# ArmazEthernet_-_Rev_A2.net
KiCad netlist of a schematic drawn in EAGLE
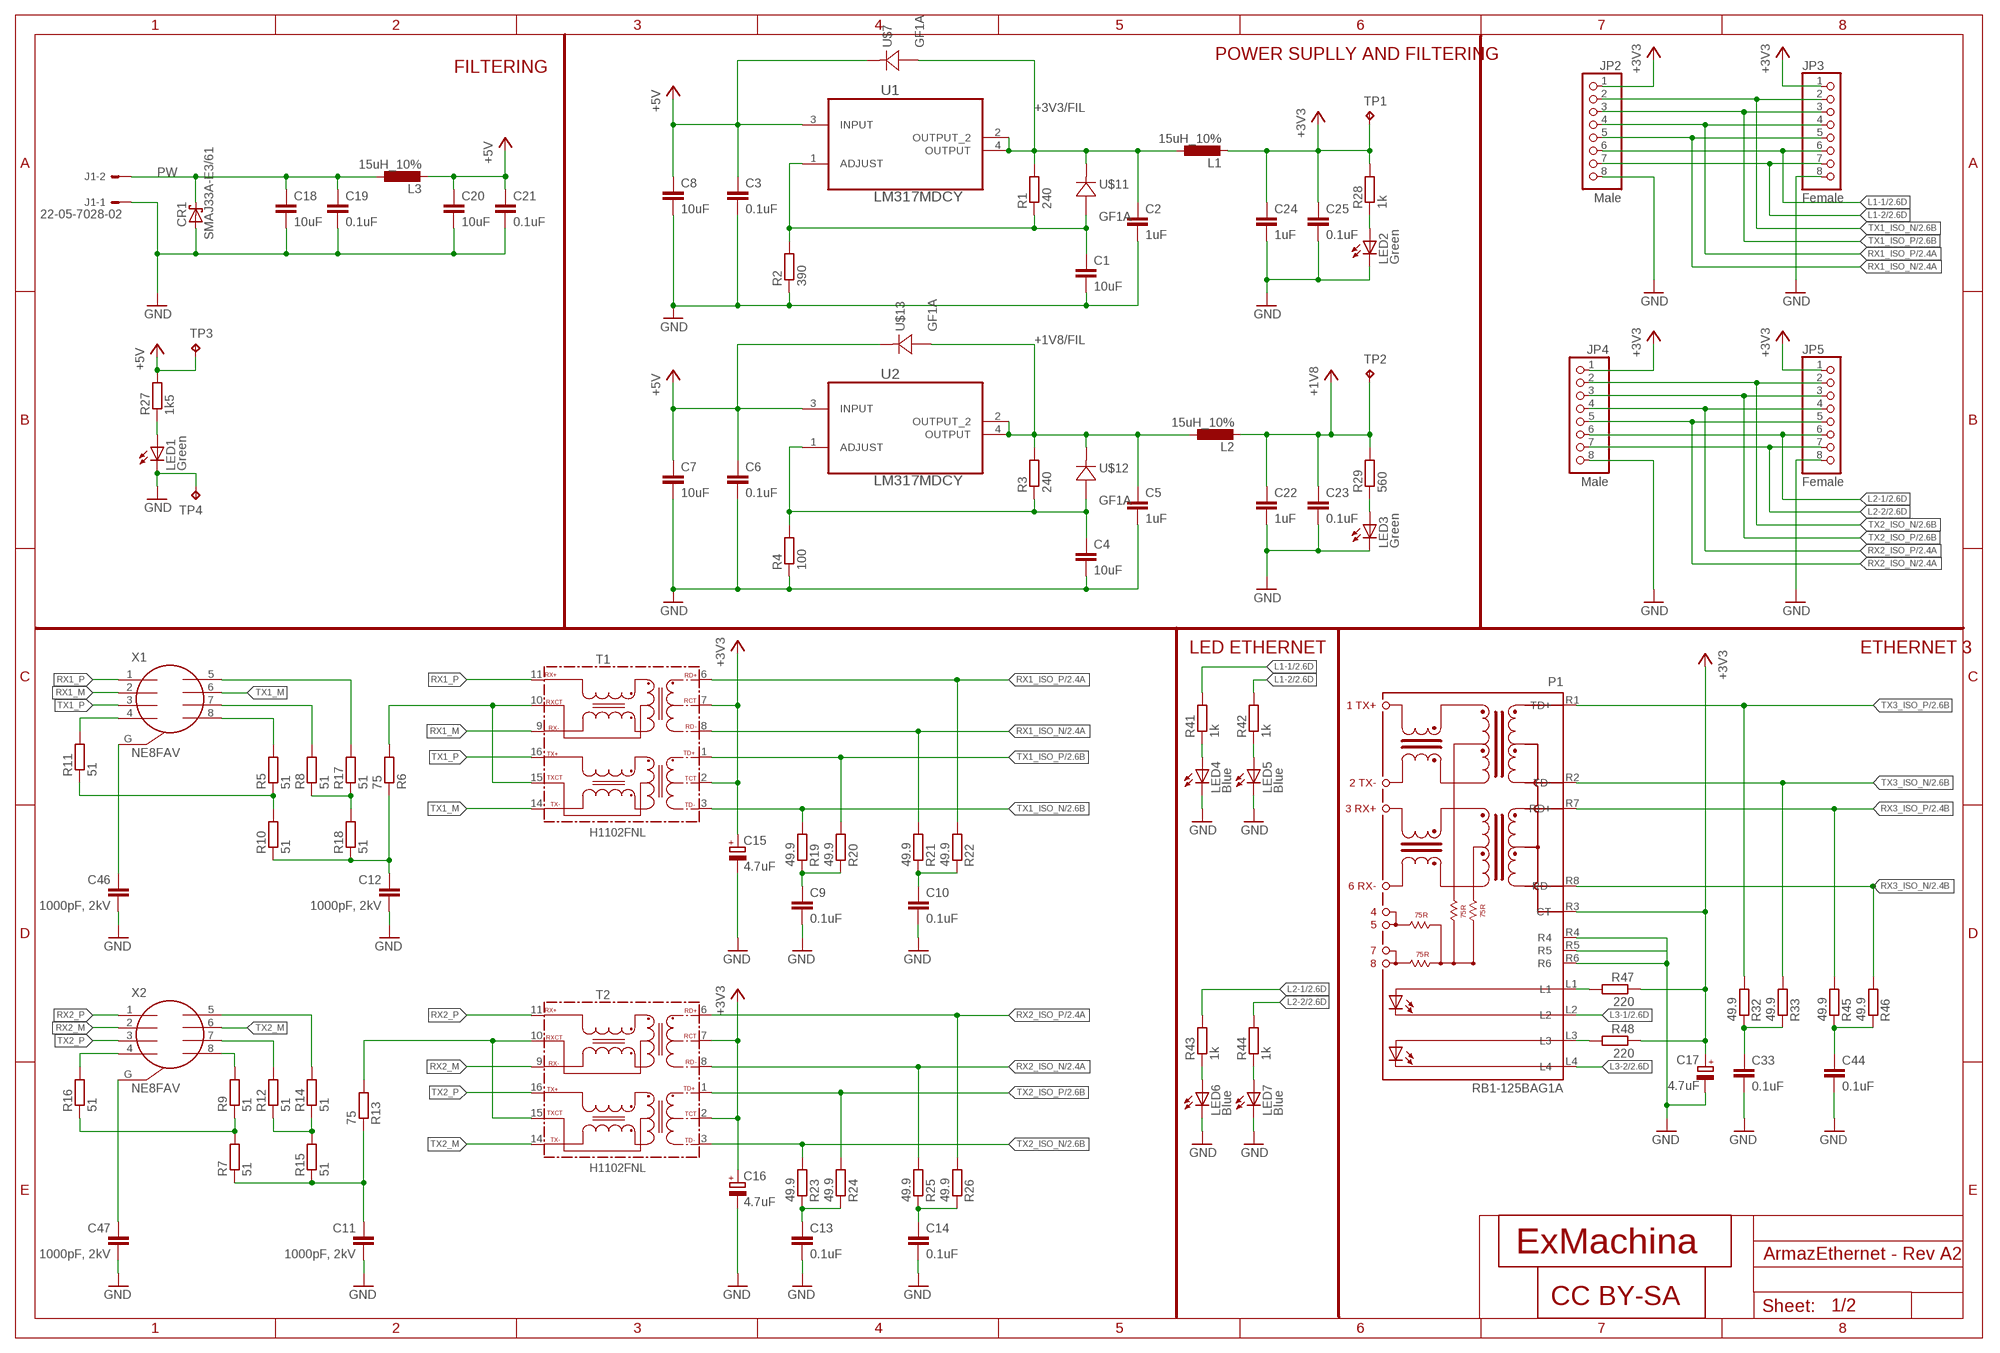
[diagram p0: schematic, sheet 1]
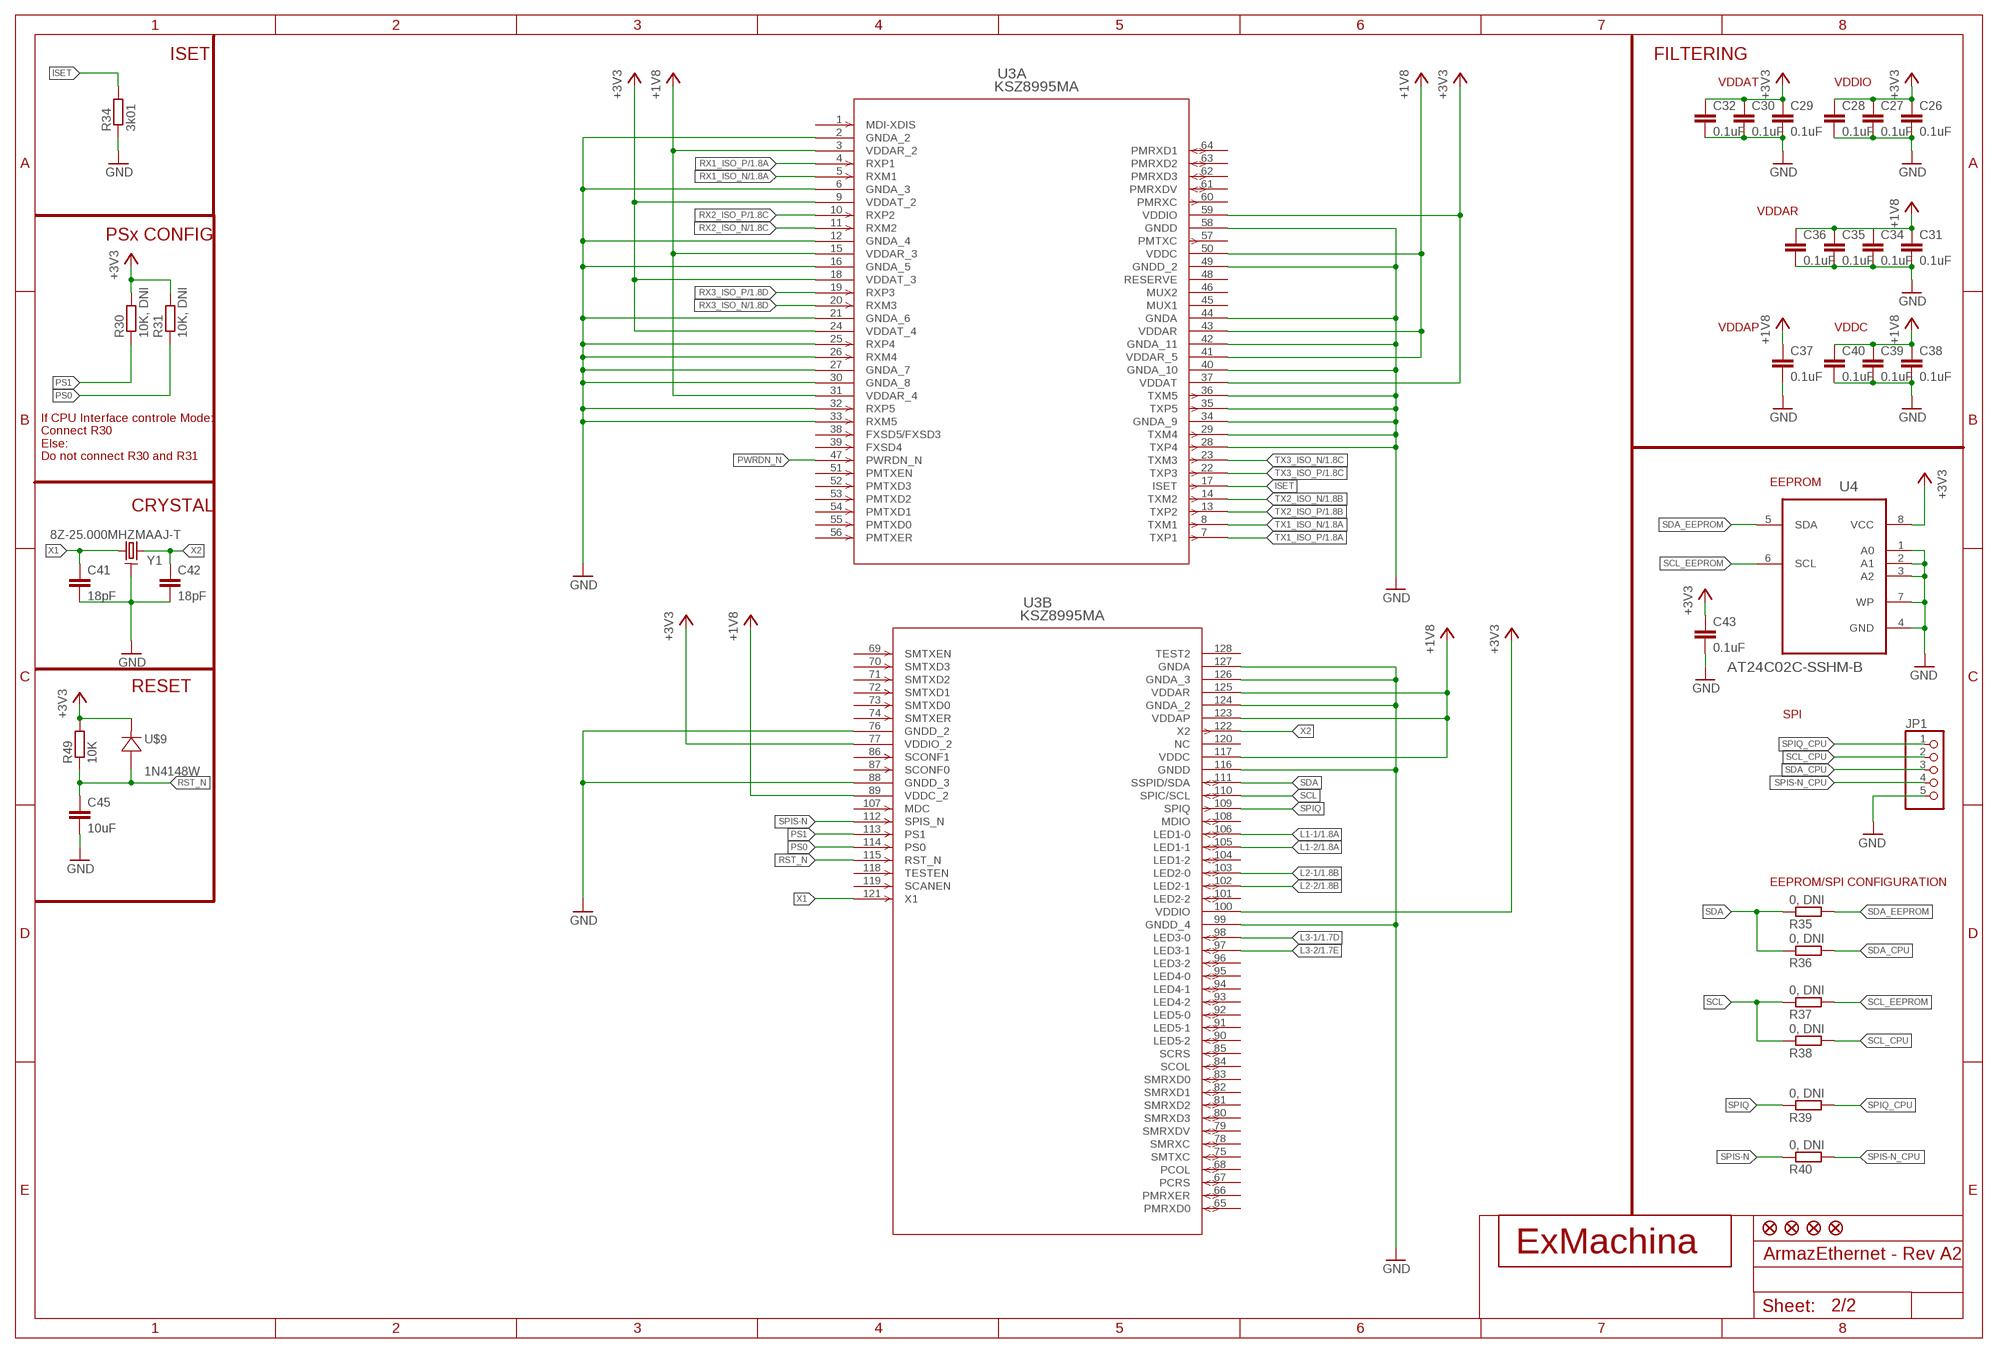
[diagram p1: schematic, sheet 2]

(export (version "E")
  (design (tool "Eeschema 10.0.6"))
  (components
    (comp (ref "C1")
      (value "10uF")
      (footprint "eagle-import:C0603")
      (fields (field (name "MPN") "MCNP16V106M5X11"))
      (libsource (lib "eagle-import") (part "C-EUC0603"))
    )
    (comp (ref "C2")
      (value "1uF")
      (footprint "eagle-import:C0603")
      (fields (field (name "MPN") "MC0603B105K160CT"))
      (libsource (lib "eagle-import") (part "C-EUC0603"))
    )
    (comp (ref "C3")
      (value "0.1uF")
      (footprint "eagle-import:C0603")
      (fields (field (name "MPN") "MC0603B104K160CT"))
      (libsource (lib "eagle-import") (part "C-EUC0603"))
    )
    (comp (ref "C4")
      (value "10uF")
      (footprint "eagle-import:C0603")
      (fields (field (name "MPN") "MCNP16V106M5X11"))
      (libsource (lib "eagle-import") (part "C-EUC0603"))
    )
    (comp (ref "C5")
      (value "1uF")
      (footprint "eagle-import:C0603")
      (fields (field (name "MPN") "MC0603B105K160CT"))
      (libsource (lib "eagle-import") (part "C-EUC0603"))
    )
    (comp (ref "C6")
      (value "0.1uF")
      (footprint "eagle-import:C0603")
      (fields (field (name "MPN") "MC0603B104K160CT"))
      (libsource (lib "eagle-import") (part "C-EUC0603"))
    )
    (comp (ref "C7")
      (value "10uF")
      (footprint "eagle-import:C0603")
      (fields (field (name "MPN") "MCNP16V106M5X11"))
      (libsource (lib "eagle-import") (part "C-EUC0603"))
    )
    (comp (ref "C8")
      (value "10uF")
      (footprint "eagle-import:C0603")
      (fields (field (name "MPN") "MCNP16V106M5X11"))
      (libsource (lib "eagle-import") (part "C-EUC0603"))
    )
    (comp (ref "C9")
      (value "0.1uF")
      (footprint "eagle-import:C0603")
      (fields (field (name "MPN") "MC0603B104K160CT"))
      (libsource (lib "eagle-import") (part "C-EUC0603"))
    )
    (comp (ref "C10")
      (value "0.1uF")
      (footprint "eagle-import:C0603")
      (fields (field (name "MPN") "MC0603B104K160CT"))
      (libsource (lib "eagle-import") (part "C-EUC0603"))
    )
    (comp (ref "C11")
      (value "1000pF, 2kV")
      (footprint "eagle-import:C1206")
      (fields (field (name "MPN") "MC1206B102K202CT"))
      (libsource (lib "eagle-import") (part "C-EUC1206"))
    )
    (comp (ref "C12")
      (value "1000pF, 2kV")
      (footprint "eagle-import:C1206")
      (fields (field (name "MPN") "MC1206B102K202CT"))
      (libsource (lib "eagle-import") (part "C-EUC1206"))
    )
    (comp (ref "C13")
      (value "0.1uF")
      (footprint "eagle-import:C0603")
      (fields (field (name "MPN") "MC0603B104K160CT"))
      (libsource (lib "eagle-import") (part "C-EUC0603"))
    )
    (comp (ref "C14")
      (value "0.1uF")
      (footprint "eagle-import:C0603")
      (fields (field (name "MPN") "MC0603B104K160CT"))
      (libsource (lib "eagle-import") (part "C-EUC0603"))
    )
    (comp (ref "C15")
      (value "4.7uF")
      (footprint "eagle-import:CT3216")
      (fields (field (name "MPN") "MCCTA475M010"))
      (libsource (lib "eagle-import") (part "CPOL-EUCT3216"))
    )
    (comp (ref "C16")
      (value "4.7uF")
      (footprint "eagle-import:CT3216")
      (fields (field (name "MPN") "MCCTA475M010"))
      (libsource (lib "eagle-import") (part "CPOL-EUCT3216"))
    )
    (comp (ref "C17")
      (value "4.7uF")
      (footprint "eagle-import:CT3216")
      (fields (field (name "MPN") "MCCTA475M010"))
      (libsource (lib "eagle-import") (part "CPOL-EUCT3216"))
    )
    (comp (ref "C18")
      (value "10uF")
      (footprint "eagle-import:C0603")
      (fields (field (name "MPN") "MCNP16V106M5X11"))
      (libsource (lib "eagle-import") (part "C-EUC0603"))
    )
    (comp (ref "C19")
      (value "0.1uF")
      (footprint "eagle-import:C0603")
      (fields (field (name "MPN") "MC0603B104K160CT"))
      (libsource (lib "eagle-import") (part "C-EUC0603"))
    )
    (comp (ref "C20")
      (value "10uF")
      (footprint "eagle-import:C0603")
      (fields (field (name "MPN") "MCNP16V106M5X11"))
      (libsource (lib "eagle-import") (part "C-EUC0603"))
    )
    (comp (ref "C21")
      (value "0.1uF")
      (footprint "eagle-import:C0603")
      (fields (field (name "MPN") "MC0603B104K160CT"))
      (libsource (lib "eagle-import") (part "C-EUC0603"))
    )
    (comp (ref "C22")
      (value "1uF")
      (footprint "eagle-import:C0603")
      (fields (field (name "MPN") "MC0603B105K160CT"))
      (libsource (lib "eagle-import") (part "C-EUC0603"))
    )
    (comp (ref "C23")
      (value "0.1uF")
      (footprint "eagle-import:C0603")
      (fields (field (name "MPN") "MC0603B104K160CT"))
      (libsource (lib "eagle-import") (part "C-EUC0603"))
    )
    (comp (ref "C24")
      (value "1uF")
      (footprint "eagle-import:C0603")
      (fields (field (name "MPN") "MC0603B105K160CT"))
      (libsource (lib "eagle-import") (part "C-EUC0603"))
    )
    (comp (ref "C25")
      (value "0.1uF")
      (footprint "eagle-import:C0603")
      (fields (field (name "MPN") "MC0603B104K160CT"))
      (libsource (lib "eagle-import") (part "C-EUC0603"))
    )
    (comp (ref "C33")
      (value "0.1uF")
      (footprint "eagle-import:C0603")
      (fields (field (name "MPN") "MC0603B104K160CT"))
      (libsource (lib "eagle-import") (part "C-EUC0603"))
    )
    (comp (ref "C44")
      (value "0.1uF")
      (footprint "eagle-import:C0603")
      (fields (field (name "MPN") "MC0603B104K160CT"))
      (libsource (lib "eagle-import") (part "C-EUC0603"))
    )
    (comp (ref "C46")
      (value "1000pF, 2kV")
      (footprint "eagle-import:C1206")
      (fields (field (name "MPN") "MC1206B102K202CT"))
      (libsource (lib "eagle-import") (part "C-EUC1206"))
    )
    (comp (ref "C47")
      (value "1000pF, 2kV")
      (footprint "eagle-import:C1206")
      (fields (field (name "MPN") "MC1206B102K202CT"))
      (libsource (lib "eagle-import") (part "C-EUC1206"))
    )
    (comp (ref "CR1")
      (value "SMAJ33A-E3/61")
      (footprint "eagle-import:DIODE_DO-214AC")
      (fields
        (field (name "RSPARTNUMBER") "7103462")
        (field (name "COPYRIGHT") "Copyright (C) 2015 Accelerated Designs. All rights reserved")
      )
      (libsource (lib "eagle-import") (part "SMAJ33A-E3/61"))
    )
    (comp (ref "J1")
      (value "22-05-7028-02")
      (footprint "eagle-import:7395-02")
      (fields (field (name "MPN") "22-05-7028") (field (name "OC_NEWARK") "25M1728"))
      (libsource (lib "eagle-import") (part "22-?-0205-7028"))
    )
    (comp (ref "JP2")
      (value "Male")
      (footprint "eagle-import:1X08")
      (fields (field (name "MPN") "2211S-08G"))
      (libsource (lib "eagle-import") (part "PINHD-1X8"))
    )
    (comp (ref "JP3")
      (value "Female")
      (footprint "eagle-import:1X08")
      (fields (field (name "MPN") "2212S-08SG-85"))
      (libsource (lib "eagle-import") (part "PINHD-1X8"))
    )
    (comp (ref "JP4")
      (value "Male")
      (footprint "eagle-import:1X08")
      (fields (field (name "MPN") "2211S-08G"))
      (libsource (lib "eagle-import") (part "PINHD-1X8"))
    )
    (comp (ref "JP5")
      (value "Female")
      (footprint "eagle-import:1X08")
      (fields (field (name "MPN") "2212S-08SG-85"))
      (libsource (lib "eagle-import") (part "PINHD-1X8"))
    )
    (comp (ref "L1")
      (value "15uH_10%")
      (footprint "eagle-import:L4532M")
      (fields (field (name "MPN") "LQH43CN150K03L"))
      (libsource (lib "eagle-import") (part "L-EUL4532C"))
    )
    (comp (ref "L2")
      (value "15uH_10%")
      (footprint "eagle-import:L4532M")
      (fields (field (name "MPN") "LQH43CN150K03L"))
      (libsource (lib "eagle-import") (part "L-EUL4532C"))
    )
    (comp (ref "L3")
      (value "15uH_10%")
      (footprint "eagle-import:L4532M")
      (fields (field (name "MPN") "LQH43CN150K03L"))
      (libsource (lib "eagle-import") (part "L-EUL4532C"))
    )
    (comp (ref "LED1")
      (value "Green")
      (footprint "eagle-import:CHIP-LED0603")
      (fields (field (name "MPN") "OVS-0604"))
      (libsource (lib "eagle-import") (part "LEDCHIP-LED0603"))
    )
    (comp (ref "LED2")
      (value "Green")
      (footprint "eagle-import:CHIP-LED0603")
      (fields (field (name "MPN") "OVS-0604"))
      (libsource (lib "eagle-import") (part "LEDCHIP-LED0603"))
    )
    (comp (ref "LED3")
      (value "Green")
      (footprint "eagle-import:CHIP-LED0603")
      (fields (field (name "MPN") "OVS-0604"))
      (libsource (lib "eagle-import") (part "LEDCHIP-LED0603"))
    )
    (comp (ref "LED4")
      (value "Blue")
      (footprint "eagle-import:CHIP-LED0603")
      (fields (field (name "MPN") "OVS-0603"))
      (libsource (lib "eagle-import") (part "LEDCHIP-LED0603"))
    )
    (comp (ref "LED5")
      (value "Blue")
      (footprint "eagle-import:CHIP-LED0603")
      (fields (field (name "MPN") "OVS-0603"))
      (libsource (lib "eagle-import") (part "LEDCHIP-LED0603"))
    )
    (comp (ref "LED6")
      (value "Blue")
      (footprint "eagle-import:CHIP-LED0603")
      (fields (field (name "MPN") "OVS-0603"))
      (libsource (lib "eagle-import") (part "LEDCHIP-LED0603"))
    )
    (comp (ref "LED7")
      (value "Blue")
      (footprint "eagle-import:CHIP-LED0603")
      (fields (field (name "MPN") "OVS-0603"))
      (libsource (lib "eagle-import") (part "LEDCHIP-LED0603"))
    )
    (comp (ref "P1")
      (value "RB1-125BAG1A")
      (footprint "eagle-import:WIZNET_RB1-125BAG1A")
      (libsource (lib "eagle-import") (part "RB1-125BAG1A"))
    )
    (comp (ref "R1")
      (value "240")
      (footprint "eagle-import:R0603")
      (fields (field (name "MPN") "MC0063W06031240R"))
      (libsource (lib "eagle-import") (part "R-EU_R0603"))
    )
    (comp (ref "R2")
      (value "390")
      (footprint "eagle-import:R0603")
      (fields (field (name "MF") "Multicomp Passives") (field (name "MPN") "MC0063W06031390R"))
      (libsource (lib "eagle-import") (part "R-EU_R0603"))
    )
    (comp (ref "R3")
      (value "240")
      (footprint "eagle-import:R0603")
      (fields (field (name "MPN") "MC0063W06031240R"))
      (libsource (lib "eagle-import") (part "R-EU_R0603"))
    )
    (comp (ref "R4")
      (value "100")
      (footprint "eagle-import:R0603")
      (fields (field (name "MF") "Multicomp Passives") (field (name "MPN") "MC0063W06031100R"))
      (libsource (lib "eagle-import") (part "R-EU_R0603"))
    )
    (comp (ref "R5")
      (value "51")
      (footprint "eagle-import:R0603")
      (fields (field (name "MF") "Multicomp Passives") (field (name "MPN") "MC0063W0603151R"))
      (libsource (lib "eagle-import") (part "R-EU_R0603"))
    )
    (comp (ref "R6")
      (value "75")
      (footprint "eagle-import:R0603")
      (fields (field (name "MF") "Multicomp Passives") (field (name "MPN") "MC0063W0603175R"))
      (libsource (lib "eagle-import") (part "R-EU_R0603"))
    )
    (comp (ref "R7")
      (value "51")
      (footprint "eagle-import:R0603")
      (fields (field (name "MF") "Multicomp Passives") (field (name "MPN") "MC0063W0603151R"))
      (libsource (lib "eagle-import") (part "R-EU_R0603"))
    )
    (comp (ref "R8")
      (value "51")
      (footprint "eagle-import:R0603")
      (fields (field (name "MF") "Multicomp Passives") (field (name "MPN") "MC0063W0603151R"))
      (libsource (lib "eagle-import") (part "R-EU_R0603"))
    )
    (comp (ref "R9")
      (value "51")
      (footprint "eagle-import:R0603")
      (fields (field (name "MF") "Multicomp Passives") (field (name "MPN") "MC0063W0603151R"))
      (libsource (lib "eagle-import") (part "R-EU_R0603"))
    )
    (comp (ref "R10")
      (value "51")
      (footprint "eagle-import:R0603")
      (fields (field (name "MF") "Multicomp Passives") (field (name "MPN") "MC0063W0603151R"))
      (libsource (lib "eagle-import") (part "R-EU_R0603"))
    )
    (comp (ref "R11")
      (value "51")
      (footprint "eagle-import:R0603")
      (fields (field (name "MF") "Multicomp Passives") (field (name "MPN") "MC0063W0603151R"))
      (libsource (lib "eagle-import") (part "R-EU_R0603"))
    )
    (comp (ref "R12")
      (value "51")
      (footprint "eagle-import:R0603")
      (fields (field (name "MF") "Multicomp Passives") (field (name "MPN") "MC0063W0603151R"))
      (libsource (lib "eagle-import") (part "R-EU_R0603"))
    )
    (comp (ref "R13")
      (value "75")
      (footprint "eagle-import:R0603")
      (fields (field (name "MF") "Multicomp Passives") (field (name "MPN") "MC0063W0603175R"))
      (libsource (lib "eagle-import") (part "R-EU_R0603"))
    )
    (comp (ref "R14")
      (value "51")
      (footprint "eagle-import:R0603")
      (fields (field (name "MF") "Multicomp Passives") (field (name "MPN") "MC0063W0603151R"))
      (libsource (lib "eagle-import") (part "R-EU_R0603"))
    )
    (comp (ref "R15")
      (value "51")
      (footprint "eagle-import:R0603")
      (fields (field (name "MF") "Multicomp Passives") (field (name "MPN") "MC0063W0603151R"))
      (libsource (lib "eagle-import") (part "R-EU_R0603"))
    )
    (comp (ref "R16")
      (value "51")
      (footprint "eagle-import:R0603")
      (fields (field (name "MF") "Multicomp Passives") (field (name "MPN") "MC0063W0603151R"))
      (libsource (lib "eagle-import") (part "R-EU_R0603"))
    )
    (comp (ref "R17")
      (value "51")
      (footprint "eagle-import:R0603")
      (fields (field (name "MF") "Multicomp Passives") (field (name "MPN") "MC0063W0603151R"))
      (libsource (lib "eagle-import") (part "R-EU_R0603"))
    )
    (comp (ref "R18")
      (value "51")
      (footprint "eagle-import:R0603")
      (fields (field (name "MF") "Multicomp Passives") (field (name "MPN") "MC0063W0603151R"))
      (libsource (lib "eagle-import") (part "R-EU_R0603"))
    )
    (comp (ref "R19")
      (value "49.9")
      (footprint "eagle-import:R0603")
      (fields (field (name "MPN") "MC0603SAF499JT5E"))
      (libsource (lib "eagle-import") (part "R-EU_R0603"))
    )
    (comp (ref "R20")
      (value "49.9")
      (footprint "eagle-import:R0603")
      (fields (field (name "MPN") "MC0603SAF499JT5E"))
      (libsource (lib "eagle-import") (part "R-EU_R0603"))
    )
    (comp (ref "R21")
      (value "49.9")
      (footprint "eagle-import:R0603")
      (fields (field (name "MPN") "MC0603SAF499JT5E"))
      (libsource (lib "eagle-import") (part "R-EU_R0603"))
    )
    (comp (ref "R22")
      (value "49.9")
      (footprint "eagle-import:R0603")
      (fields (field (name "MPN") "MC0603SAF499JT5E"))
      (libsource (lib "eagle-import") (part "R-EU_R0603"))
    )
    (comp (ref "R23")
      (value "49.9")
      (footprint "eagle-import:R0603")
      (fields (field (name "MPN") "MC0603SAF499JT5E"))
      (libsource (lib "eagle-import") (part "R-EU_R0603"))
    )
    (comp (ref "R24")
      (value "49.9")
      (footprint "eagle-import:R0603")
      (fields (field (name "MPN") "MC0603SAF499JT5E"))
      (libsource (lib "eagle-import") (part "R-EU_R0603"))
    )
    (comp (ref "R25")
      (value "49.9")
      (footprint "eagle-import:R0603")
      (fields (field (name "MPN") "MC0603SAF499JT5E"))
      (libsource (lib "eagle-import") (part "R-EU_R0603"))
    )
    (comp (ref "R26")
      (value "49.9")
      (footprint "eagle-import:R0603")
      (fields (field (name "MPN") "MC0603SAF499JT5E"))
      (libsource (lib "eagle-import") (part "R-EU_R0603"))
    )
    (comp (ref "R27")
      (value "1k5")
      (footprint "eagle-import:R0603")
      (fields (field (name "MF") "Multicomp Passives") (field (name "MPN") "MC0063W060311K5"))
      (libsource (lib "eagle-import") (part "R-EU_R0603"))
    )
    (comp (ref "R28")
      (value "1k")
      (footprint "eagle-import:R0603")
      (fields (field (name "MPN") "MCMR06X1001FTL"))
      (libsource (lib "eagle-import") (part "R-EU_R0603"))
    )
    (comp (ref "R29")
      (value "560")
      (footprint "eagle-import:R0603")
      (fields (field (name "MPN") "MCMR06X1501FTL"))
      (libsource (lib "eagle-import") (part "R-EU_R0603"))
    )
    (comp (ref "R32")
      (value "49.9")
      (footprint "eagle-import:R0603")
      (fields (field (name "MPN") "MC0603SAF499JT5E"))
      (libsource (lib "eagle-import") (part "R-EU_R0603"))
    )
    (comp (ref "R33")
      (value "49.9")
      (footprint "eagle-import:R0603")
      (fields (field (name "MPN") "MC0603SAF499JT5E"))
      (libsource (lib "eagle-import") (part "R-EU_R0603"))
    )
    (comp (ref "R41")
      (value "1k")
      (footprint "eagle-import:R0603")
      (fields (field (name "MPN") "MCMR06X1001FTL"))
      (libsource (lib "eagle-import") (part "R-EU_R0603"))
    )
    (comp (ref "R42")
      (value "1k")
      (footprint "eagle-import:R0603")
      (fields (field (name "MPN") "MCMR06X1001FTL"))
      (libsource (lib "eagle-import") (part "R-EU_R0603"))
    )
    (comp (ref "R43")
      (value "1k")
      (footprint "eagle-import:R0603")
      (fields (field (name "MPN") "MCMR06X1001FTL"))
      (libsource (lib "eagle-import") (part "R-EU_R0603"))
    )
    (comp (ref "R44")
      (value "1k")
      (footprint "eagle-import:R0603")
      (fields (field (name "MPN") "MCMR06X1001FTL"))
      (libsource (lib "eagle-import") (part "R-EU_R0603"))
    )
    (comp (ref "R45")
      (value "49.9")
      (footprint "eagle-import:R0603")
      (fields (field (name "MPN") "MC0603SAF499JT5E"))
      (libsource (lib "eagle-import") (part "R-EU_R0603"))
    )
    (comp (ref "R46")
      (value "49.9")
      (footprint "eagle-import:R0603")
      (fields (field (name "MPN") "MC0603SAF499JT5E"))
      (libsource (lib "eagle-import") (part "R-EU_R0603"))
    )
    (comp (ref "R47")
      (value "220")
      (footprint "eagle-import:R0603")
      (fields (field (name "MF") "Multicomp Passives") (field (name "MPN") "MC0063W06031220R"))
      (libsource (lib "eagle-import") (part "R-EU_R0603"))
    )
    (comp (ref "R48")
      (value "220")
      (footprint "eagle-import:R0603")
      (fields (field (name "MF") "Multicomp Passives") (field (name "MPN") "MC0063W06031220R"))
      (libsource (lib "eagle-import") (part "R-EU_R0603"))
    )
    (comp (ref "T1")
      (value "H1102FNL")
      (footprint "eagle-import:HXXXX")
      (libsource (lib "eagle-import") (part "H1102FNL"))
    )
    (comp (ref "T2")
      (value "H1102FNL")
      (footprint "eagle-import:HXXXX")
      (libsource (lib "eagle-import") (part "H1102FNL"))
    )
    (comp (ref "TP1")
      (value "TPB1,27")
      (footprint "eagle-import:B1,27")
      (libsource (lib "eagle-import") (part "TPB1,27"))
    )
    (comp (ref "TP2")
      (value "TPB1,27")
      (footprint "eagle-import:B1,27")
      (libsource (lib "eagle-import") (part "TPB1,27"))
    )
    (comp (ref "TP3")
      (value "TPB1,27")
      (footprint "eagle-import:B1,27")
      (libsource (lib "eagle-import") (part "TPB1,27"))
    )
    (comp (ref "TP4")
      (value "TPB1,27")
      (footprint "eagle-import:B1,27")
      (libsource (lib "eagle-import") (part "TPB1,27"))
    )
    (comp (ref "U$5")
      (value "EXMACHINA-LOGO-NAME")
      (footprint "eagle-import:EXM-LOGO-BASELINE")
      (libsource (lib "eagle-import") (part "EXMACHINA-LOGO-NAME"))
    )
    (comp (ref "U$6")
      (value "CC-BY-SA")
      (footprint "eagle-import:CC-BY-SA")
      (libsource (lib "eagle-import") (part "CC-BY-SA"))
    )
    (comp (ref "U$7")
      (value "GF1A")
      (footprint "eagle-import:DO-214BA")
      (fields (field (name "MPN") "GF1B-E3/67A"))
      (libsource (lib "eagle-import") (part "GF1A"))
    )
    (comp (ref "U$11")
      (value "GF1A")
      (footprint "eagle-import:DO-214BA")
      (fields (field (name "MPN") "GF1B-E3/67A"))
      (libsource (lib "eagle-import") (part "GF1A"))
    )
    (comp (ref "U$12")
      (value "GF1A")
      (footprint "eagle-import:DO-214BA")
      (fields (field (name "MPN") "GF1B-E3/67A"))
      (libsource (lib "eagle-import") (part "GF1A"))
    )
    (comp (ref "U$13")
      (value "GF1A")
      (footprint "eagle-import:DO-214BA")
      (fields (field (name "MPN") "GF1B-E3/67A"))
      (libsource (lib "eagle-import") (part "GF1A"))
    )
    (comp (ref "U1")
      (value "LM317MDCY")
      (footprint "eagle-import:SOT230P700X180-4N")
      (fields (field (name "MF") "TEXAS INSTRUMENTS"))
      (libsource (lib "eagle-import") (part "LM317MDCY"))
    )
    (comp (ref "U2")
      (value "LM317MDCY")
      (footprint "eagle-import:SOT230P700X180-4N")
      (fields (field (name "MF") "TEXAS INSTRUMENTS"))
      (libsource (lib "eagle-import") (part "LM317MDCY"))
    )
    (comp (ref "X1")
      (value "NE8FAV")
      (footprint "eagle-import:NE8FAV")
      (fields (field (name "MF") "NEUTRIK"))
      (libsource (lib "eagle-import") (part "NE8FAV"))
    )
    (comp (ref "X2")
      (value "NE8FAV")
      (footprint "eagle-import:NE8FAV")
      (fields (field (name "MF") "NEUTRIK"))
      (libsource (lib "eagle-import") (part "NE8FAV"))
    )
    (comp (ref "C26")
      (value "0.1uF")
      (footprint "eagle-import:C0603")
      (fields (field (name "MPN") "MC0603B104K160CT"))
      (libsource (lib "eagle-import") (part "C-EUC0603"))
    )
    (comp (ref "C27")
      (value "0.1uF")
      (footprint "eagle-import:C0603")
      (fields (field (name "MPN") "MC0603B104K160CT"))
      (libsource (lib "eagle-import") (part "C-EUC0603"))
    )
    (comp (ref "C28")
      (value "0.1uF")
      (footprint "eagle-import:C0603")
      (fields (field (name "MPN") "MC0603B104K160CT"))
      (libsource (lib "eagle-import") (part "C-EUC0603"))
    )
    (comp (ref "C29")
      (value "0.1uF")
      (footprint "eagle-import:C0603")
      (fields (field (name "MPN") "MC0603B104K160CT"))
      (libsource (lib "eagle-import") (part "C-EUC0603"))
    )
    (comp (ref "C30")
      (value "0.1uF")
      (footprint "eagle-import:C0603")
      (fields (field (name "MPN") "MC0603B104K160CT"))
      (libsource (lib "eagle-import") (part "C-EUC0603"))
    )
    (comp (ref "C31")
      (value "0.1uF")
      (footprint "eagle-import:C0603")
      (fields (field (name "MPN") "MC0603B104K160CT"))
      (libsource (lib "eagle-import") (part "C-EUC0603"))
    )
    (comp (ref "C32")
      (value "0.1uF")
      (footprint "eagle-import:C0603")
      (fields (field (name "MPN") "MC0603B104K160CT"))
      (libsource (lib "eagle-import") (part "C-EUC0603"))
    )
    (comp (ref "C34")
      (value "0.1uF")
      (footprint "eagle-import:C0603")
      (fields (field (name "MPN") "MC0603B104K160CT"))
      (libsource (lib "eagle-import") (part "C-EUC0603"))
    )
    (comp (ref "C35")
      (value "0.1uF")
      (footprint "eagle-import:C0603")
      (fields (field (name "MPN") "MC0603B104K160CT"))
      (libsource (lib "eagle-import") (part "C-EUC0603"))
    )
    (comp (ref "C36")
      (value "0.1uF")
      (footprint "eagle-import:C0603")
      (fields (field (name "MPN") "MC0603B104K160CT"))
      (libsource (lib "eagle-import") (part "C-EUC0603"))
    )
    (comp (ref "C37")
      (value "0.1uF")
      (footprint "eagle-import:C0603")
      (fields (field (name "MPN") "MC0603B104K160CT"))
      (libsource (lib "eagle-import") (part "C-EUC0603"))
    )
    (comp (ref "C38")
      (value "0.1uF")
      (footprint "eagle-import:C0603")
      (fields (field (name "MPN") "MC0603B104K160CT"))
      (libsource (lib "eagle-import") (part "C-EUC0603"))
    )
    (comp (ref "C39")
      (value "0.1uF")
      (footprint "eagle-import:C0603")
      (fields (field (name "MPN") "MC0603B104K160CT"))
      (libsource (lib "eagle-import") (part "C-EUC0603"))
    )
    (comp (ref "C40")
      (value "0.1uF")
      (footprint "eagle-import:C0603")
      (fields (field (name "MPN") "MC0603B104K160CT"))
      (libsource (lib "eagle-import") (part "C-EUC0603"))
    )
    (comp (ref "C41")
      (value "18pF")
      (footprint "eagle-import:C0603")
      (fields (field (name "MPN") "MC0603N180J500CT"))
      (libsource (lib "eagle-import") (part "C-EUC0603"))
    )
    (comp (ref "C42")
      (value "18pF")
      (footprint "eagle-import:C0603")
      (fields (field (name "MPN") "MC0603N180J500CT"))
      (libsource (lib "eagle-import") (part "C-EUC0603"))
    )
    (comp (ref "C43")
      (value "0.1uF")
      (footprint "eagle-import:C0603")
      (fields (field (name "MPN") "MC0603B104K160CT"))
      (libsource (lib "eagle-import") (part "C-EUC0603"))
    )
    (comp (ref "C45")
      (value "10uF")
      (footprint "eagle-import:C0603")
      (fields (field (name "MPN") "MCNP16V106M5X11"))
      (libsource (lib "eagle-import") (part "C-EUC0603"))
    )
    (comp (ref "JP1")
      (value "PINHD-1X5")
      (footprint "eagle-import:1X05")
      (fields (field (name "MPN") "M20-9990545"))
      (libsource (lib "eagle-import") (part "PINHD-1X5"))
    )
    (comp (ref "JP7")
      (value "FIDUCIAL1X2")
      (footprint "eagle-import:FIDUCIAL-1X2")
      (libsource (lib "eagle-import") (part "FIDUCIAL1X2"))
    )
    (comp (ref "JP8")
      (value "FIDUCIAL1X2")
      (footprint "eagle-import:FIDUCIAL-1X2")
      (libsource (lib "eagle-import") (part "FIDUCIAL1X2"))
    )
    (comp (ref "JP9")
      (value "FIDUCIAL1X2")
      (footprint "eagle-import:FIDUCIAL-1X2")
      (libsource (lib "eagle-import") (part "FIDUCIAL1X2"))
    )
    (comp (ref "JP10")
      (value "FIDUCIAL1X2")
      (footprint "eagle-import:FIDUCIAL-1X2")
      (libsource (lib "eagle-import") (part "FIDUCIAL1X2"))
    )
    (comp (ref "R30")
      (value "10K, DNI")
      (footprint "eagle-import:R0603")
      (fields (field (name "MF") "Multicomp Passives") (field (name "MPN") "MC0063W0603110K"))
      (libsource (lib "eagle-import") (part "R-EU_R0603"))
    )
    (comp (ref "R31")
      (value "10K, DNI")
      (footprint "eagle-import:R0603")
      (fields (field (name "MF") "Multicomp Passives") (field (name "MPN") "MC0063W0603110K"))
      (libsource (lib "eagle-import") (part "R-EU_R0603"))
    )
    (comp (ref "R34")
      (value "3k01")
      (footprint "eagle-import:R0603")
      (fields (field (name "MPN") "MC0063W060313K01"))
      (libsource (lib "eagle-import") (part "R-EU_R0603"))
    )
    (comp (ref "R35")
      (value "0, DNI")
      (footprint "eagle-import:R0603")
      (fields (field (name "MF") "Multicomp Passives") (field (name "MPN") "MC0603WG00000T5E-TC"))
      (libsource (lib "eagle-import") (part "R-EU_R0603"))
    )
    (comp (ref "R36")
      (value "0, DNI")
      (footprint "eagle-import:R0603")
      (fields (field (name "MF") "Multicomp Passives") (field (name "MPN") "MC0603WG00000T5E-TC"))
      (libsource (lib "eagle-import") (part "R-EU_R0603"))
    )
    (comp (ref "R37")
      (value "0, DNI")
      (footprint "eagle-import:R0603")
      (fields (field (name "MF") "Multicomp Passives") (field (name "MPN") "MC0603WG00000T5E-TC"))
      (libsource (lib "eagle-import") (part "R-EU_R0603"))
    )
    (comp (ref "R38")
      (value "0, DNI")
      (footprint "eagle-import:R0603")
      (fields (field (name "MF") "Multicomp Passives") (field (name "MPN") "MC0603WG00000T5E-TC"))
      (libsource (lib "eagle-import") (part "R-EU_R0603"))
    )
    (comp (ref "R39")
      (value "0, DNI")
      (footprint "eagle-import:R0603")
      (fields (field (name "MF") "Multicomp Passives") (field (name "MPN") "MC0603WG00000T5E-TC"))
      (libsource (lib "eagle-import") (part "R-EU_R0603"))
    )
    (comp (ref "R40")
      (value "0, DNI")
      (footprint "eagle-import:R0603")
      (fields (field (name "MF") "Multicomp Passives") (field (name "MPN") "MC0603WG00000T5E-TC"))
      (libsource (lib "eagle-import") (part "R-EU_R0603"))
    )
    (comp (ref "R49")
      (value "10K")
      (footprint "eagle-import:R0603")
      (fields (field (name "MF") "Multicomp Passives") (field (name "MPN") "MC0063W0603110K"))
      (libsource (lib "eagle-import") (part "R-EU_R0603"))
    )
    (comp (ref "U$8")
      (value "EXMACHINA-LOGO-NAME")
      (footprint "eagle-import:EXM-LOGO-BASELINE")
      (libsource (lib "eagle-import") (part "EXMACHINA-LOGO-NAME"))
    )
    (comp (ref "U$9")
      (value "1N4148W")
      (footprint "eagle-import:SOD-123_MINI-SMA")
      (libsource (lib "eagle-import") (part "1N4148W"))
    )
    (comp (ref "U3")
      (value "KSZ8995MA")
      (footprint "eagle-import:PQFP-128_MQL")
      (fields
        (field (name "MANUFACTURER_PART_NUMBER") "ksz8995ma")
        (field (name "MPN") "KSZ8995MA")
        (field (name "OC_NEWARK") "70Y9044")
        (field (name "COPYRIGHT") "Copyright (C) 2015 Accelerated Designs. All rights reserved")
      )
      (libsource (lib "eagle-import") (part "KSZ8995MA"))
    )
    (comp (ref "U4")
      (value "AT24C02C-SSHM-B")
      (footprint "eagle-import:SOIC127P600X175-8N")
      (libsource (lib "eagle-import") (part "AT24C02C-SSHM-B"))
    )
    (comp (ref "Y1")
      (value "8Z-25.000MHZMAAJ-T")
      (footprint "eagle-import:SMD2.5X2")
      (fields (field (name "MPN") "8Z-25.000MAAJ-T"))
      (libsource (lib "eagle-import") (part "8Z-25.000MHZMAAJ-T"))
    )
  )
  (nets
    (net (code "1") (name "+1V8") (class "Default")
      (node (ref "C22") (pin "1") (pinfunction "1_1") (pintype "passive"))
      (node (ref "C23") (pin "1") (pinfunction "1_1") (pintype "passive"))
      (node (ref "C31") (pin "1") (pinfunction "1_1") (pintype "passive"))
      (node (ref "C34") (pin "1") (pinfunction "1_1") (pintype "passive"))
      (node (ref "C35") (pin "1") (pinfunction "1_1") (pintype "passive"))
      (node (ref "C36") (pin "1") (pinfunction "1_1") (pintype "passive"))
      (node (ref "C37") (pin "1") (pinfunction "1_1") (pintype "passive"))
      (node (ref "C38") (pin "1") (pinfunction "1_1") (pintype "passive"))
      (node (ref "C39") (pin "1") (pinfunction "1_1") (pintype "passive"))
      (node (ref "C40") (pin "1") (pinfunction "1_1") (pintype "passive"))
      (node (ref "L2") (pin "2") (pinfunction "2_2") (pintype "passive"))
      (node (ref "R29") (pin "2") (pinfunction "2_2") (pintype "passive"))
      (node (ref "TP2") (pin "TP") (pinfunction "TP_TP") (pintype "input"))
      (node (ref "U3") (pin "117") (pinfunction "VDDC_117") (pintype "power_in"))
      (node (ref "U3") (pin "123") (pinfunction "VDDAP_123") (pintype "power_in"))
      (node (ref "U3") (pin "125") (pinfunction "VDDAR_125") (pintype "power_in"))
      (node (ref "U3") (pin "15") (pinfunction "VDDAR_3_15") (pintype "power_in"))
      (node (ref "U3") (pin "3") (pinfunction "VDDAR_2_3") (pintype "power_in"))
      (node (ref "U3") (pin "31") (pinfunction "VDDAR_4_31") (pintype "power_in"))
      (node (ref "U3") (pin "41") (pinfunction "VDDAR_5_41") (pintype "power_in"))
      (node (ref "U3") (pin "43") (pinfunction "VDDAR_43") (pintype "power_in"))
      (node (ref "U3") (pin "50") (pinfunction "VDDC_50") (pintype "power_in"))
      (node (ref "U3") (pin "89") (pinfunction "VDDC_2_89") (pintype "power_in"))
    )
    (net (code "2") (name "+1V8{slash}FIL") (class "Default")
      (node (ref "C5") (pin "1") (pinfunction "1_1") (pintype "passive"))
      (node (ref "L2") (pin "1") (pinfunction "1_1") (pintype "passive"))
      (node (ref "R3") (pin "2") (pinfunction "2_2") (pintype "passive"))
      (node (ref "U$12") (pin "C") (pinfunction "1_C") (pintype "passive"))
      (node (ref "U$13") (pin "A") (pinfunction "2_A") (pintype "passive"))
      (node (ref "U2") (pin "2") (pinfunction "OUTPUT_2_2") (pintype "output"))
      (node (ref "U2") (pin "4") (pinfunction "OUTPUT_4") (pintype "output"))
    )
    (net (code "3") (name "+3V3") (class "Default")
      (node (ref "C15") (pin "+") (pinfunction "+_+") (pintype "passive"))
      (node (ref "C16") (pin "+") (pinfunction "+_+") (pintype "passive"))
      (node (ref "C17") (pin "+") (pinfunction "+_+") (pintype "passive"))
      (node (ref "C24") (pin "1") (pinfunction "1_1") (pintype "passive"))
      (node (ref "C25") (pin "1") (pinfunction "1_1") (pintype "passive"))
      (node (ref "C26") (pin "1") (pinfunction "1_1") (pintype "passive"))
      (node (ref "C27") (pin "1") (pinfunction "1_1") (pintype "passive"))
      (node (ref "C28") (pin "1") (pinfunction "1_1") (pintype "passive"))
      (node (ref "C29") (pin "1") (pinfunction "1_1") (pintype "passive"))
      (node (ref "C30") (pin "1") (pinfunction "1_1") (pintype "passive"))
      (node (ref "C32") (pin "1") (pinfunction "1_1") (pintype "passive"))
      (node (ref "C43") (pin "1") (pinfunction "1_1") (pintype "passive"))
      (node (ref "JP2") (pin "1") (pinfunction "1_1") (pintype "passive"))
      (node (ref "JP3") (pin "1") (pinfunction "1_1") (pintype "passive"))
      (node (ref "JP4") (pin "1") (pinfunction "1_1") (pintype "passive"))
      (node (ref "JP5") (pin "1") (pinfunction "1_1") (pintype "passive"))
      (node (ref "L1") (pin "2") (pinfunction "2_2") (pintype "passive"))
      (node (ref "P1") (pin "R3") (pinfunction "CT_R3") (pintype "input"))
      (node (ref "R28") (pin "2") (pinfunction "2_2") (pintype "passive"))
      (node (ref "R30") (pin "2") (pinfunction "2_2") (pintype "passive"))
      (node (ref "R31") (pin "2") (pinfunction "2_2") (pintype "passive"))
      (node (ref "R47") (pin "1") (pinfunction "1_1") (pintype "passive"))
      (node (ref "R48") (pin "1") (pinfunction "1_1") (pintype "passive"))
      (node (ref "R49") (pin "2") (pinfunction "2_2") (pintype "passive"))
      (node (ref "T1") (pin "2") (pinfunction "TCT_2") (pintype "bidirectional"))
      (node (ref "T1") (pin "7") (pinfunction "RCT_7") (pintype "bidirectional"))
      (node (ref "T2") (pin "2") (pinfunction "TCT_2") (pintype "bidirectional"))
      (node (ref "T2") (pin "7") (pinfunction "RCT_7") (pintype "bidirectional"))
      (node (ref "TP1") (pin "TP") (pinfunction "TP_TP") (pintype "input"))
      (node (ref "U$9") (pin "C") (pinfunction "1_C") (pintype "passive"))
      (node (ref "U3") (pin "100") (pinfunction "VDDIO_100") (pintype "power_in"))
      (node (ref "U3") (pin "18") (pinfunction "VDDAT_3_18") (pintype "power_in"))
      (node (ref "U3") (pin "24") (pinfunction "VDDAT_4_24") (pintype "power_in"))
      (node (ref "U3") (pin "37") (pinfunction "VDDAT_37") (pintype "power_in"))
      (node (ref "U3") (pin "59") (pinfunction "VDDIO_59") (pintype "power_in"))
      (node (ref "U3") (pin "77") (pinfunction "VDDIO_2_77") (pintype "power_in"))
      (node (ref "U3") (pin "9") (pinfunction "VDDAT_2_9") (pintype "power_in"))
      (node (ref "U4") (pin "8") (pinfunction "VCC_8") (pintype "power_in"))
    )
    (net (code "4") (name "+3V3{slash}FIL") (class "Default")
      (node (ref "C2") (pin "1") (pinfunction "1_1") (pintype "passive"))
      (node (ref "L1") (pin "1") (pinfunction "1_1") (pintype "passive"))
      (node (ref "R1") (pin "2") (pinfunction "2_2") (pintype "passive"))
      (node (ref "U$11") (pin "C") (pinfunction "1_C") (pintype "passive"))
      (node (ref "U$7") (pin "A") (pinfunction "2_A") (pintype "passive"))
      (node (ref "U1") (pin "2") (pinfunction "OUTPUT_2_2") (pintype "output"))
      (node (ref "U1") (pin "4") (pinfunction "OUTPUT_4") (pintype "output"))
    )
    (net (code "5") (name "+5V") (class "Default")
      (node (ref "C20") (pin "1") (pinfunction "1_1") (pintype "passive"))
      (node (ref "C21") (pin "1") (pinfunction "1_1") (pintype "passive"))
      (node (ref "C3") (pin "1") (pinfunction "1_1") (pintype "passive"))
      (node (ref "C6") (pin "1") (pinfunction "1_1") (pintype "passive"))
      (node (ref "C7") (pin "1") (pinfunction "1_1") (pintype "passive"))
      (node (ref "C8") (pin "1") (pinfunction "1_1") (pintype "passive"))
      (node (ref "L3") (pin "2") (pinfunction "2_2") (pintype "passive"))
      (node (ref "R27") (pin "2") (pinfunction "2_2") (pintype "passive"))
      (node (ref "TP3") (pin "TP") (pinfunction "TP_TP") (pintype "input"))
      (node (ref "U$13") (pin "C") (pinfunction "1_C") (pintype "passive"))
      (node (ref "U$7") (pin "C") (pinfunction "1_C") (pintype "passive"))
      (node (ref "U1") (pin "3") (pinfunction "INPUT_3") (pintype "input"))
      (node (ref "U2") (pin "3") (pinfunction "INPUT_3") (pintype "input"))
    )
    (net (code "6") (name "GND") (class "Default")
      (node (ref "C1") (pin "2") (pinfunction "2_2") (pintype "passive"))
      (node (ref "C10") (pin "2") (pinfunction "2_2") (pintype "passive"))
      (node (ref "C11") (pin "2") (pinfunction "2_2") (pintype "passive"))
      (node (ref "C12") (pin "2") (pinfunction "2_2") (pintype "passive"))
      (node (ref "C13") (pin "2") (pinfunction "2_2") (pintype "passive"))
      (node (ref "C14") (pin "2") (pinfunction "2_2") (pintype "passive"))
      (node (ref "C15") (pin "-") (pinfunction "-_-") (pintype "passive"))
      (node (ref "C16") (pin "-") (pinfunction "-_-") (pintype "passive"))
      (node (ref "C17") (pin "-") (pinfunction "-_-") (pintype "passive"))
      (node (ref "C18") (pin "2") (pinfunction "2_2") (pintype "passive"))
      (node (ref "C19") (pin "2") (pinfunction "2_2") (pintype "passive"))
      (node (ref "C2") (pin "2") (pinfunction "2_2") (pintype "passive"))
      (node (ref "C20") (pin "2") (pinfunction "2_2") (pintype "passive"))
      (node (ref "C21") (pin "2") (pinfunction "2_2") (pintype "passive"))
      (node (ref "C22") (pin "2") (pinfunction "2_2") (pintype "passive"))
      (node (ref "C23") (pin "2") (pinfunction "2_2") (pintype "passive"))
      (node (ref "C24") (pin "2") (pinfunction "2_2") (pintype "passive"))
      (node (ref "C25") (pin "2") (pinfunction "2_2") (pintype "passive"))
      (node (ref "C26") (pin "2") (pinfunction "2_2") (pintype "passive"))
      (node (ref "C27") (pin "2") (pinfunction "2_2") (pintype "passive"))
      (node (ref "C28") (pin "2") (pinfunction "2_2") (pintype "passive"))
      (node (ref "C29") (pin "2") (pinfunction "2_2") (pintype "passive"))
      (node (ref "C3") (pin "2") (pinfunction "2_2") (pintype "passive"))
      (node (ref "C30") (pin "2") (pinfunction "2_2") (pintype "passive"))
      (node (ref "C31") (pin "2") (pinfunction "2_2") (pintype "passive"))
      (node (ref "C32") (pin "2") (pinfunction "2_2") (pintype "passive"))
      (node (ref "C33") (pin "2") (pinfunction "2_2") (pintype "passive"))
      (node (ref "C34") (pin "2") (pinfunction "2_2") (pintype "passive"))
      (node (ref "C35") (pin "2") (pinfunction "2_2") (pintype "passive"))
      (node (ref "C36") (pin "2") (pinfunction "2_2") (pintype "passive"))
      (node (ref "C37") (pin "2") (pinfunction "2_2") (pintype "passive"))
      (node (ref "C38") (pin "2") (pinfunction "2_2") (pintype "passive"))
      (node (ref "C39") (pin "2") (pinfunction "2_2") (pintype "passive"))
      (node (ref "C4") (pin "2") (pinfunction "2_2") (pintype "passive"))
      (node (ref "C40") (pin "2") (pinfunction "2_2") (pintype "passive"))
      (node (ref "C41") (pin "2") (pinfunction "2_2") (pintype "passive"))
      (node (ref "C42") (pin "2") (pinfunction "2_2") (pintype "passive"))
      (node (ref "C43") (pin "2") (pinfunction "2_2") (pintype "passive"))
      (node (ref "C44") (pin "2") (pinfunction "2_2") (pintype "passive"))
      (node (ref "C45") (pin "2") (pinfunction "2_2") (pintype "passive"))
      (node (ref "C46") (pin "2") (pinfunction "2_2") (pintype "passive"))
      (node (ref "C47") (pin "2") (pinfunction "2_2") (pintype "passive"))
      (node (ref "C5") (pin "2") (pinfunction "2_2") (pintype "passive"))
      (node (ref "C6") (pin "2") (pinfunction "2_2") (pintype "passive"))
      (node (ref "C7") (pin "2") (pinfunction "2_2") (pintype "passive"))
      (node (ref "C8") (pin "2") (pinfunction "2_2") (pintype "passive"))
      (node (ref "C9") (pin "2") (pinfunction "2_2") (pintype "passive"))
      (node (ref "CR1") (pin "2") (pinfunction "A_2") (pintype "passive"))
      (node (ref "J1") (pin "1") (pinfunction "S_1") (pintype "passive"))
      (node (ref "JP1") (pin "5") (pinfunction "5_5") (pintype "passive"))
      (node (ref "JP2") (pin "8") (pinfunction "8_8") (pintype "passive"))
      (node (ref "JP3") (pin "8") (pinfunction "8_8") (pintype "passive"))
      (node (ref "JP4") (pin "8") (pinfunction "8_8") (pintype "passive"))
      (node (ref "JP5") (pin "8") (pinfunction "8_8") (pintype "passive"))
      (node (ref "LED1") (pin "C") (pinfunction "C_C") (pintype "passive"))
      (node (ref "LED2") (pin "C") (pinfunction "C_C") (pintype "passive"))
      (node (ref "LED3") (pin "C") (pinfunction "C_C") (pintype "passive"))
      (node (ref "LED4") (pin "C") (pinfunction "C_C") (pintype "passive"))
      (node (ref "LED5") (pin "C") (pinfunction "C_C") (pintype "passive"))
      (node (ref "LED6") (pin "C") (pinfunction "C_C") (pintype "passive"))
      (node (ref "LED7") (pin "C") (pinfunction "C_C") (pintype "passive"))
      (node (ref "P1") (pin "R4") (pinfunction "R4_R4") (pintype "input"))
      (node (ref "P1") (pin "R5") (pinfunction "R5_R5") (pintype "input"))
      (node (ref "P1") (pin "R6") (pinfunction "R6_R6") (pintype "input"))
      (node (ref "R2") (pin "1") (pinfunction "1_1") (pintype "passive"))
      (node (ref "R34") (pin "1") (pinfunction "1_1") (pintype "passive"))
      (node (ref "R4") (pin "1") (pinfunction "1_1") (pintype "passive"))
      (node (ref "TP4") (pin "TP") (pinfunction "TP_TP") (pintype "input"))
      (node (ref "U3") (pin "116") (pinfunction "GNDD_116") (pintype "power_in"))
      (node (ref "U3") (pin "12") (pinfunction "GNDA_4_12") (pintype "power_in"))
      (node (ref "U3") (pin "124") (pinfunction "GNDA_2_124") (pintype "power_in"))
      (node (ref "U3") (pin "126") (pinfunction "GNDA_3_126") (pintype "power_in"))
      (node (ref "U3") (pin "127") (pinfunction "GNDA_127") (pintype "power_in"))
      (node (ref "U3") (pin "16") (pinfunction "GNDA_5_16") (pintype "power_in"))
      (node (ref "U3") (pin "2") (pinfunction "GNDA_2_2") (pintype "power_in"))
      (node (ref "U3") (pin "21") (pinfunction "GNDA_6_21") (pintype "power_in"))
      (node (ref "U3") (pin "25") (pinfunction "RXP4_25") (pintype "input"))
      (node (ref "U3") (pin "26") (pinfunction "RXM4_26") (pintype "input"))
      (node (ref "U3") (pin "27") (pinfunction "GNDA_7_27") (pintype "power_in"))
      (node (ref "U3") (pin "28") (pinfunction "TXP4_28") (pintype "output"))
      (node (ref "U3") (pin "29") (pinfunction "TXM4_29") (pintype "output"))
      (node (ref "U3") (pin "30") (pinfunction "GNDA_8_30") (pintype "power_in"))
      (node (ref "U3") (pin "32") (pinfunction "RXP5_32") (pintype "input"))
      (node (ref "U3") (pin "33") (pinfunction "RXM5_33") (pintype "input"))
      (node (ref "U3") (pin "34") (pinfunction "GNDA_9_34") (pintype "power_in"))
      (node (ref "U3") (pin "35") (pinfunction "TXP5_35") (pintype "output"))
      (node (ref "U3") (pin "36") (pinfunction "TXM5_36") (pintype "output"))
      (node (ref "U3") (pin "40") (pinfunction "GNDA_10_40") (pintype "power_in"))
      (node (ref "U3") (pin "42") (pinfunction "GNDA_11_42") (pintype "power_in"))
      (node (ref "U3") (pin "44") (pinfunction "GNDA_44") (pintype "power_in"))
      (node (ref "U3") (pin "49") (pinfunction "GNDD_2_49") (pintype "passive"))
      (node (ref "U3") (pin "58") (pinfunction "GNDD_58") (pintype "power_in"))
      (node (ref "U3") (pin "6") (pinfunction "GNDA_3_6") (pintype "power_in"))
      (node (ref "U3") (pin "76") (pinfunction "GNDD_2_76") (pintype "power_in"))
      (node (ref "U3") (pin "88") (pinfunction "GNDD_3_88") (pintype "power_in"))
      (node (ref "U3") (pin "99") (pinfunction "GNDD_4_99") (pintype "power_in"))
      (node (ref "U4") (pin "1") (pinfunction "A0_1") (pintype "input"))
      (node (ref "U4") (pin "2") (pinfunction "A1_2") (pintype "input"))
      (node (ref "U4") (pin "3") (pinfunction "A2_3") (pintype "input"))
      (node (ref "U4") (pin "4") (pinfunction "GND_4") (pintype "power_in"))
      (node (ref "U4") (pin "7") (pinfunction "WP_7") (pintype "input"))
      (node (ref "Y1") (pin "2") (pinfunction "2_2") (pintype "passive"))
      (node (ref "Y1") (pin "4") (pinfunction "2_4") (pintype "passive"))
    )
    (net (code "7") (name "ISET") (class "Default")
      (node (ref "R34") (pin "2") (pinfunction "2_2") (pintype "passive"))
      (node (ref "U3") (pin "17") (pinfunction "ISET_17") (pintype "output"))
    )
    (net (code "8") (name "L1-1") (class "Default")
      (node (ref "JP2") (pin "6") (pinfunction "6_6") (pintype "passive"))
      (node (ref "JP3") (pin "6") (pinfunction "6_6") (pintype "passive"))
      (node (ref "R41") (pin "2") (pinfunction "2_2") (pintype "passive"))
      (node (ref "U3") (pin "106") (pinfunction "LED1-0_106") (pintype "bidirectional"))
    )
    (net (code "9") (name "L1-2") (class "Default")
      (node (ref "JP2") (pin "7") (pinfunction "7_7") (pintype "passive"))
      (node (ref "JP3") (pin "7") (pinfunction "7_7") (pintype "passive"))
      (node (ref "R42") (pin "2") (pinfunction "2_2") (pintype "passive"))
      (node (ref "U3") (pin "105") (pinfunction "LED1-1_105") (pintype "bidirectional"))
    )
    (net (code "10") (name "L2-1") (class "Default")
      (node (ref "JP4") (pin "6") (pinfunction "6_6") (pintype "passive"))
      (node (ref "JP5") (pin "6") (pinfunction "6_6") (pintype "passive"))
      (node (ref "R43") (pin "2") (pinfunction "2_2") (pintype "passive"))
      (node (ref "U3") (pin "103") (pinfunction "LED2-0_103") (pintype "bidirectional"))
    )
    (net (code "11") (name "L2-2") (class "Default")
      (node (ref "JP4") (pin "7") (pinfunction "7_7") (pintype "passive"))
      (node (ref "JP5") (pin "7") (pinfunction "7_7") (pintype "passive"))
      (node (ref "R44") (pin "2") (pinfunction "2_2") (pintype "passive"))
      (node (ref "U3") (pin "102") (pinfunction "LED2-1_102") (pintype "bidirectional"))
    )
    (net (code "12") (name "L3-1") (class "Default")
      (node (ref "P1") (pin "L2") (pinfunction "L2_L2") (pintype "passive"))
      (node (ref "U3") (pin "98") (pinfunction "LED3-0_98") (pintype "bidirectional"))
    )
    (net (code "13") (name "L3-2") (class "Default")
      (node (ref "P1") (pin "L4") (pinfunction "L4_L4") (pintype "passive"))
      (node (ref "U3") (pin "97") (pinfunction "LED3-1_97") (pintype "bidirectional"))
    )
    (net (code "14") (name "Net-(C9-Pad1)") (class "Default")
      (node (ref "C9") (pin "1") (pinfunction "1_1") (pintype "passive"))
      (node (ref "R19") (pin "1") (pinfunction "1_1") (pintype "passive"))
      (node (ref "R20") (pin "1") (pinfunction "1_1") (pintype "passive"))
    )
    (net (code "15") (name "Net-(C10-Pad1)") (class "Default")
      (node (ref "C10") (pin "1") (pinfunction "1_1") (pintype "passive"))
      (node (ref "R21") (pin "1") (pinfunction "1_1") (pintype "passive"))
      (node (ref "R22") (pin "1") (pinfunction "1_1") (pintype "passive"))
    )
    (net (code "16") (name "Net-(C11-Pad1)") (class "Default")
      (node (ref "C11") (pin "1") (pinfunction "1_1") (pintype "passive"))
      (node (ref "R13") (pin "1") (pinfunction "1_1") (pintype "passive"))
      (node (ref "R15") (pin "1") (pinfunction "1_1") (pintype "passive"))
      (node (ref "R7") (pin "1") (pinfunction "1_1") (pintype "passive"))
    )
    (net (code "17") (name "Net-(C12-Pad1)") (class "Default")
      (node (ref "C12") (pin "1") (pinfunction "1_1") (pintype "passive"))
      (node (ref "R10") (pin "1") (pinfunction "1_1") (pintype "passive"))
      (node (ref "R18") (pin "1") (pinfunction "1_1") (pintype "passive"))
      (node (ref "R6") (pin "1") (pinfunction "1_1") (pintype "passive"))
    )
    (net (code "18") (name "Net-(C13-Pad1)") (class "Default")
      (node (ref "C13") (pin "1") (pinfunction "1_1") (pintype "passive"))
      (node (ref "R23") (pin "1") (pinfunction "1_1") (pintype "passive"))
      (node (ref "R24") (pin "1") (pinfunction "1_1") (pintype "passive"))
    )
    (net (code "19") (name "Net-(C14-Pad1)") (class "Default")
      (node (ref "C14") (pin "1") (pinfunction "1_1") (pintype "passive"))
      (node (ref "R25") (pin "1") (pinfunction "1_1") (pintype "passive"))
      (node (ref "R26") (pin "1") (pinfunction "1_1") (pintype "passive"))
    )
    (net (code "20") (name "Net-(C33-Pad1)") (class "Default")
      (node (ref "C33") (pin "1") (pinfunction "1_1") (pintype "passive"))
      (node (ref "R32") (pin "1") (pinfunction "1_1") (pintype "passive"))
      (node (ref "R33") (pin "1") (pinfunction "1_1") (pintype "passive"))
    )
    (net (code "21") (name "Net-(C44-Pad1)") (class "Default")
      (node (ref "C44") (pin "1") (pinfunction "1_1") (pintype "passive"))
      (node (ref "R45") (pin "1") (pinfunction "1_1") (pintype "passive"))
      (node (ref "R46") (pin "1") (pinfunction "1_1") (pintype "passive"))
    )
    (net (code "22") (name "Net-(C46-Pad1)") (class "Default")
      (node (ref "C46") (pin "1") (pinfunction "1_1") (pintype "passive"))
      (node (ref "X1") (pin "G") (pinfunction "G_G") (pintype "passive"))
    )
    (net (code "23") (name "Net-(C47-Pad1)") (class "Default")
      (node (ref "C47") (pin "1") (pinfunction "1_1") (pintype "passive"))
      (node (ref "X2") (pin "G") (pinfunction "G_G") (pintype "passive"))
    )
    (net (code "24") (name "Net-(LED1-PadA)") (class "Default")
      (node (ref "LED1") (pin "A") (pinfunction "A_A") (pintype "passive"))
      (node (ref "R27") (pin "1") (pinfunction "1_1") (pintype "passive"))
    )
    (net (code "25") (name "Net-(LED2-PadA)") (class "Default")
      (node (ref "LED2") (pin "A") (pinfunction "A_A") (pintype "passive"))
      (node (ref "R28") (pin "1") (pinfunction "1_1") (pintype "passive"))
    )
    (net (code "26") (name "Net-(LED3-PadA)") (class "Default")
      (node (ref "LED3") (pin "A") (pinfunction "A_A") (pintype "passive"))
      (node (ref "R29") (pin "1") (pinfunction "1_1") (pintype "passive"))
    )
    (net (code "27") (name "Net-(LED4-PadA)") (class "Default")
      (node (ref "LED4") (pin "A") (pinfunction "A_A") (pintype "passive"))
      (node (ref "R41") (pin "1") (pinfunction "1_1") (pintype "passive"))
    )
    (net (code "28") (name "Net-(LED5-PadA)") (class "Default")
      (node (ref "LED5") (pin "A") (pinfunction "A_A") (pintype "passive"))
      (node (ref "R42") (pin "1") (pinfunction "1_1") (pintype "passive"))
    )
    (net (code "29") (name "Net-(LED6-PadA)") (class "Default")
      (node (ref "LED6") (pin "A") (pinfunction "A_A") (pintype "passive"))
      (node (ref "R43") (pin "1") (pinfunction "1_1") (pintype "passive"))
    )
    (net (code "30") (name "Net-(LED7-PadA)") (class "Default")
      (node (ref "LED7") (pin "A") (pinfunction "A_A") (pintype "passive"))
      (node (ref "R44") (pin "1") (pinfunction "1_1") (pintype "passive"))
    )
    (net (code "31") (name "Net-(P1-PadL1)") (class "Default")
      (node (ref "P1") (pin "L1") (pinfunction "L1_L1") (pintype "passive"))
      (node (ref "R47") (pin "2") (pinfunction "2_2") (pintype "passive"))
    )
    (net (code "32") (name "Net-(P1-PadL3)") (class "Default")
      (node (ref "P1") (pin "L3") (pinfunction "L3_L3") (pintype "passive"))
      (node (ref "R48") (pin "2") (pinfunction "2_2") (pintype "passive"))
    )
    (net (code "33") (name "Net-(R5-Pad2)") (class "Default")
      (node (ref "R5") (pin "2") (pinfunction "2_2") (pintype "passive"))
      (node (ref "X1") (pin "8") (pinfunction "8_8") (pintype "passive"))
    )
    (net (code "34") (name "Net-(R8-Pad2)") (class "Default")
      (node (ref "R8") (pin "2") (pinfunction "2_2") (pintype "passive"))
      (node (ref "X1") (pin "7") (pinfunction "7_7") (pintype "passive"))
    )
    (net (code "35") (name "Net-(R9-Pad2)") (class "Default")
      (node (ref "R9") (pin "2") (pinfunction "2_2") (pintype "passive"))
      (node (ref "X2") (pin "8") (pinfunction "8_8") (pintype "passive"))
    )
    (net (code "36") (name "Net-(R10-Pad2)") (class "Default")
      (node (ref "R10") (pin "2") (pinfunction "2_2") (pintype "passive"))
      (node (ref "R11") (pin "1") (pinfunction "1_1") (pintype "passive"))
      (node (ref "R5") (pin "1") (pinfunction "1_1") (pintype "passive"))
    )
    (net (code "37") (name "Net-(R11-Pad2)") (class "Default")
      (node (ref "R11") (pin "2") (pinfunction "2_2") (pintype "passive"))
      (node (ref "X1") (pin "4") (pinfunction "4_4") (pintype "passive"))
    )
    (net (code "38") (name "Net-(R12-Pad1)") (class "Default")
      (node (ref "R12") (pin "1") (pinfunction "1_1") (pintype "passive"))
      (node (ref "R14") (pin "1") (pinfunction "1_1") (pintype "passive"))
      (node (ref "R15") (pin "2") (pinfunction "2_2") (pintype "passive"))
    )
    (net (code "39") (name "Net-(R12-Pad2)") (class "Default")
      (node (ref "R12") (pin "2") (pinfunction "2_2") (pintype "passive"))
      (node (ref "X2") (pin "7") (pinfunction "7_7") (pintype "passive"))
    )
    (net (code "40") (name "Net-(R14-Pad2)") (class "Default")
      (node (ref "R14") (pin "2") (pinfunction "2_2") (pintype "passive"))
      (node (ref "X2") (pin "5") (pinfunction "5_5") (pintype "passive"))
    )
    (net (code "41") (name "Net-(R16-Pad1)") (class "Default")
      (node (ref "R16") (pin "1") (pinfunction "1_1") (pintype "passive"))
      (node (ref "R7") (pin "2") (pinfunction "2_2") (pintype "passive"))
      (node (ref "R9") (pin "1") (pinfunction "1_1") (pintype "passive"))
    )
    (net (code "42") (name "Net-(R16-Pad2)") (class "Default")
      (node (ref "R16") (pin "2") (pinfunction "2_2") (pintype "passive"))
      (node (ref "X2") (pin "4") (pinfunction "4_4") (pintype "passive"))
    )
    (net (code "43") (name "Net-(R17-Pad1)") (class "Default")
      (node (ref "R17") (pin "1") (pinfunction "1_1") (pintype "passive"))
      (node (ref "R18") (pin "2") (pinfunction "2_2") (pintype "passive"))
      (node (ref "R8") (pin "1") (pinfunction "1_1") (pintype "passive"))
    )
    (net (code "44") (name "Net-(R17-Pad2)") (class "Default")
      (node (ref "R17") (pin "2") (pinfunction "2_2") (pintype "passive"))
      (node (ref "X1") (pin "5") (pinfunction "5_5") (pintype "passive"))
    )
    (net (code "45") (name "Net-(T1-RXCT)") (class "Default")
      (node (ref "R6") (pin "2") (pinfunction "2_2") (pintype "passive"))
      (node (ref "T1") (pin "10") (pinfunction "RXCT_10") (pintype "bidirectional"))
      (node (ref "T1") (pin "15") (pinfunction "TXCT_15") (pintype "bidirectional"))
    )
    (net (code "46") (name "Net-(T2-RXCT)") (class "Default")
      (node (ref "R13") (pin "2") (pinfunction "2_2") (pintype "passive"))
      (node (ref "T2") (pin "10") (pinfunction "RXCT_10") (pintype "bidirectional"))
      (node (ref "T2") (pin "15") (pinfunction "TXCT_15") (pintype "bidirectional"))
    )
    (net (code "47") (name "Net-(U$11-2)") (class "Default")
      (node (ref "C1") (pin "1") (pinfunction "1_1") (pintype "passive"))
      (node (ref "R1") (pin "1") (pinfunction "1_1") (pintype "passive"))
      (node (ref "R2") (pin "2") (pinfunction "2_2") (pintype "passive"))
      (node (ref "U$11") (pin "A") (pinfunction "2_A") (pintype "passive"))
      (node (ref "U1") (pin "1") (pinfunction "ADJUST_1") (pintype "input"))
    )
    (net (code "48") (name "Net-(U$12-2)") (class "Default")
      (node (ref "C4") (pin "1") (pinfunction "1_1") (pintype "passive"))
      (node (ref "R3") (pin "1") (pinfunction "1_1") (pintype "passive"))
      (node (ref "R4") (pin "2") (pinfunction "2_2") (pintype "passive"))
      (node (ref "U$12") (pin "A") (pinfunction "2_A") (pintype "passive"))
      (node (ref "U2") (pin "1") (pinfunction "ADJUST_1") (pintype "input"))
    )
    (net (code "49") (name "PS0") (class "Default")
      (node (ref "R31") (pin "1") (pinfunction "1_1") (pintype "passive"))
      (node (ref "U3") (pin "114") (pinfunction "PS0_114") (pintype "input"))
    )
    (net (code "50") (name "PS1") (class "Default")
      (node (ref "R30") (pin "1") (pinfunction "1_1") (pintype "passive"))
      (node (ref "U3") (pin "113") (pinfunction "PS1_113") (pintype "input"))
    )
    (net (code "51") (name "PW") (class "Default")
      (node (ref "C18") (pin "1") (pinfunction "1_1") (pintype "passive"))
      (node (ref "C19") (pin "1") (pinfunction "1_1") (pintype "passive"))
      (node (ref "CR1") (pin "1") (pinfunction "C_1") (pintype "passive"))
      (node (ref "J1") (pin "2") (pinfunction "S_2") (pintype "passive"))
      (node (ref "L3") (pin "1") (pinfunction "1_1") (pintype "passive"))
    )
    (net (code "52") (name "PWRDN_N") (class "Default")
      (node (ref "U3") (pin "47") (pinfunction "PWRDN_N_47") (pintype "input"))
    )
    (net (code "53") (name "RST_N") (class "Default")
      (node (ref "C45") (pin "1") (pinfunction "1_1") (pintype "passive"))
      (node (ref "R49") (pin "1") (pinfunction "1_1") (pintype "passive"))
      (node (ref "U$9") (pin "A") (pinfunction "2_A") (pintype "passive"))
      (node (ref "U3") (pin "115") (pinfunction "RST_N_115") (pintype "input"))
    )
    (net (code "54") (name "RX1_ISO_N") (class "Default")
      (node (ref "JP2") (pin "5") (pinfunction "5_5") (pintype "passive"))
      (node (ref "JP3") (pin "5") (pinfunction "5_5") (pintype "passive"))
      (node (ref "R21") (pin "2") (pinfunction "2_2") (pintype "passive"))
      (node (ref "T1") (pin "8") (pinfunction "RD-_8") (pintype "bidirectional"))
      (node (ref "U3") (pin "5") (pinfunction "RXM1_5") (pintype "input"))
    )
    (net (code "55") (name "RX1_ISO_P") (class "Default")
      (node (ref "JP2") (pin "4") (pinfunction "4_4") (pintype "passive"))
      (node (ref "JP3") (pin "4") (pinfunction "4_4") (pintype "passive"))
      (node (ref "R22") (pin "2") (pinfunction "2_2") (pintype "passive"))
      (node (ref "T1") (pin "6") (pinfunction "RD+_6") (pintype "bidirectional"))
      (node (ref "U3") (pin "4") (pinfunction "RXP1_4") (pintype "input"))
    )
    (net (code "56") (name "RX1_M") (class "Default")
      (node (ref "T1") (pin "9") (pinfunction "RX-_9") (pintype "bidirectional"))
      (node (ref "X1") (pin "2") (pinfunction "2_2") (pintype "passive"))
    )
    (net (code "57") (name "RX1_P") (class "Default")
      (node (ref "T1") (pin "11") (pinfunction "RX+_11") (pintype "bidirectional"))
      (node (ref "X1") (pin "1") (pinfunction "1_1") (pintype "passive"))
    )
    (net (code "58") (name "RX2_ISO_N") (class "Default")
      (node (ref "JP4") (pin "5") (pinfunction "5_5") (pintype "passive"))
      (node (ref "JP5") (pin "5") (pinfunction "5_5") (pintype "passive"))
      (node (ref "R25") (pin "2") (pinfunction "2_2") (pintype "passive"))
      (node (ref "T2") (pin "8") (pinfunction "RD-_8") (pintype "bidirectional"))
      (node (ref "U3") (pin "11") (pinfunction "RXM2_11") (pintype "input"))
    )
    (net (code "59") (name "RX2_ISO_P") (class "Default")
      (node (ref "JP4") (pin "4") (pinfunction "4_4") (pintype "passive"))
      (node (ref "JP5") (pin "4") (pinfunction "4_4") (pintype "passive"))
      (node (ref "R26") (pin "2") (pinfunction "2_2") (pintype "passive"))
      (node (ref "T2") (pin "6") (pinfunction "RD+_6") (pintype "bidirectional"))
      (node (ref "U3") (pin "10") (pinfunction "RXP2_10") (pintype "input"))
    )
    (net (code "60") (name "RX2_M") (class "Default")
      (node (ref "T2") (pin "9") (pinfunction "RX-_9") (pintype "bidirectional"))
      (node (ref "X2") (pin "2") (pinfunction "2_2") (pintype "passive"))
    )
    (net (code "61") (name "RX2_P") (class "Default")
      (node (ref "T2") (pin "11") (pinfunction "RX+_11") (pintype "bidirectional"))
      (node (ref "X2") (pin "1") (pinfunction "1_1") (pintype "passive"))
    )
    (net (code "62") (name "RX3_ISO_N") (class "Default")
      (node (ref "P1") (pin "R8") (pinfunction "RD-_R8") (pintype "input"))
      (node (ref "R46") (pin "2") (pinfunction "2_2") (pintype "passive"))
      (node (ref "U3") (pin "20") (pinfunction "RXM3_20") (pintype "input"))
    )
    (net (code "63") (name "RX3_ISO_P") (class "Default")
      (node (ref "P1") (pin "R7") (pinfunction "RD+_R7") (pintype "input"))
      (node (ref "R45") (pin "2") (pinfunction "2_2") (pintype "passive"))
      (node (ref "U3") (pin "19") (pinfunction "RXP3_19") (pintype "input"))
    )
    (net (code "64") (name "SCL") (class "Default")
      (node (ref "R37") (pin "1") (pinfunction "1_1") (pintype "passive"))
      (node (ref "R38") (pin "1") (pinfunction "1_1") (pintype "passive"))
      (node (ref "U3") (pin "110") (pinfunction "SPIC/SCL_110") (pintype "bidirectional"))
    )
    (net (code "65") (name "SCL_CPU") (class "Default")
      (node (ref "JP1") (pin "2") (pinfunction "2_2") (pintype "passive"))
      (node (ref "R38") (pin "2") (pinfunction "2_2") (pintype "passive"))
    )
    (net (code "66") (name "SCL_EEPROM") (class "Default")
      (node (ref "R37") (pin "2") (pinfunction "2_2") (pintype "passive"))
      (node (ref "U4") (pin "6") (pinfunction "SCL_6") (pintype "input"))
    )
    (net (code "67") (name "SDA") (class "Default")
      (node (ref "R35") (pin "1") (pinfunction "1_1") (pintype "passive"))
      (node (ref "R36") (pin "1") (pinfunction "1_1") (pintype "passive"))
      (node (ref "U3") (pin "111") (pinfunction "SSPID/SDA_111") (pintype "bidirectional"))
    )
    (net (code "68") (name "SDA_CPU") (class "Default")
      (node (ref "JP1") (pin "3") (pinfunction "3_3") (pintype "passive"))
      (node (ref "R36") (pin "2") (pinfunction "2_2") (pintype "passive"))
    )
    (net (code "69") (name "SDA_EEPROM") (class "Default")
      (node (ref "R35") (pin "2") (pinfunction "2_2") (pintype "passive"))
      (node (ref "U4") (pin "5") (pinfunction "SDA_5") (pintype "bidirectional"))
    )
    (net (code "70") (name "SPIQ") (class "Default")
      (node (ref "R39") (pin "1") (pinfunction "1_1") (pintype "passive"))
      (node (ref "U3") (pin "109") (pinfunction "SPIQ_109") (pintype "output"))
    )
    (net (code "71") (name "SPIQ_CPU") (class "Default")
      (node (ref "JP1") (pin "1") (pinfunction "1_1") (pintype "passive"))
      (node (ref "R39") (pin "2") (pinfunction "2_2") (pintype "passive"))
    )
    (net (code "72") (name "SPIS-N") (class "Default")
      (node (ref "R40") (pin "1") (pinfunction "1_1") (pintype "passive"))
      (node (ref "U3") (pin "112") (pinfunction "SPIS_N_112") (pintype "input"))
    )
    (net (code "73") (name "SPIS-N_CPU") (class "Default")
      (node (ref "JP1") (pin "4") (pinfunction "4_4") (pintype "passive"))
      (node (ref "R40") (pin "2") (pinfunction "2_2") (pintype "passive"))
    )
    (net (code "74") (name "TX1_ISO_N") (class "Default")
      (node (ref "JP2") (pin "2") (pinfunction "2_2") (pintype "passive"))
      (node (ref "JP3") (pin "2") (pinfunction "2_2") (pintype "passive"))
      (node (ref "R19") (pin "2") (pinfunction "2_2") (pintype "passive"))
      (node (ref "T1") (pin "3") (pinfunction "TD-_3") (pintype "bidirectional"))
      (node (ref "U3") (pin "8") (pinfunction "TXM1_8") (pintype "output"))
    )
    (net (code "75") (name "TX1_ISO_P") (class "Default")
      (node (ref "JP2") (pin "3") (pinfunction "3_3") (pintype "passive"))
      (node (ref "JP3") (pin "3") (pinfunction "3_3") (pintype "passive"))
      (node (ref "R20") (pin "2") (pinfunction "2_2") (pintype "passive"))
      (node (ref "T1") (pin "1") (pinfunction "TD+_1") (pintype "bidirectional"))
      (node (ref "U3") (pin "7") (pinfunction "TXP1_7") (pintype "output"))
    )
    (net (code "76") (name "TX1_M") (class "Default")
      (node (ref "T1") (pin "14") (pinfunction "TX-_14") (pintype "bidirectional"))
      (node (ref "X1") (pin "6") (pinfunction "6_6") (pintype "passive"))
    )
    (net (code "77") (name "TX1_P") (class "Default")
      (node (ref "T1") (pin "16") (pinfunction "TX+_16") (pintype "bidirectional"))
      (node (ref "X1") (pin "3") (pinfunction "3_3") (pintype "passive"))
    )
    (net (code "78") (name "TX2_ISO_N") (class "Default")
      (node (ref "JP4") (pin "2") (pinfunction "2_2") (pintype "passive"))
      (node (ref "JP5") (pin "2") (pinfunction "2_2") (pintype "passive"))
      (node (ref "R23") (pin "2") (pinfunction "2_2") (pintype "passive"))
      (node (ref "T2") (pin "3") (pinfunction "TD-_3") (pintype "bidirectional"))
      (node (ref "U3") (pin "14") (pinfunction "TXM2_14") (pintype "output"))
    )
    (net (code "79") (name "TX2_ISO_P") (class "Default")
      (node (ref "JP4") (pin "3") (pinfunction "3_3") (pintype "passive"))
      (node (ref "JP5") (pin "3") (pinfunction "3_3") (pintype "passive"))
      (node (ref "R24") (pin "2") (pinfunction "2_2") (pintype "passive"))
      (node (ref "T2") (pin "1") (pinfunction "TD+_1") (pintype "bidirectional"))
      (node (ref "U3") (pin "13") (pinfunction "TXP2_13") (pintype "output"))
    )
    (net (code "80") (name "TX2_M") (class "Default")
      (node (ref "T2") (pin "14") (pinfunction "TX-_14") (pintype "bidirectional"))
      (node (ref "X2") (pin "6") (pinfunction "6_6") (pintype "passive"))
    )
    (net (code "81") (name "TX2_P") (class "Default")
      (node (ref "T2") (pin "16") (pinfunction "TX+_16") (pintype "bidirectional"))
      (node (ref "X2") (pin "3") (pinfunction "3_3") (pintype "passive"))
    )
    (net (code "82") (name "TX3_ISO_N") (class "Default")
      (node (ref "P1") (pin "R2") (pinfunction "TD-_R2") (pintype "input"))
      (node (ref "R33") (pin "2") (pinfunction "2_2") (pintype "passive"))
      (node (ref "U3") (pin "23") (pinfunction "TXM3_23") (pintype "output"))
    )
    (net (code "83") (name "TX3_ISO_P") (class "Default")
      (node (ref "P1") (pin "R1") (pinfunction "TD+_R1") (pintype "input"))
      (node (ref "R32") (pin "2") (pinfunction "2_2") (pintype "passive"))
      (node (ref "U3") (pin "22") (pinfunction "TXP3_22") (pintype "output"))
    )
    (net (code "84") (name "X1") (class "Default")
      (node (ref "C41") (pin "1") (pinfunction "1_1") (pintype "passive"))
      (node (ref "U3") (pin "121") (pinfunction "X1_121") (pintype "input"))
      (node (ref "Y1") (pin "1") (pinfunction "1_1") (pintype "passive"))
    )
    (net (code "85") (name "X2") (class "Default")
      (node (ref "C42") (pin "1") (pinfunction "1_1") (pintype "passive"))
      (node (ref "U3") (pin "122") (pinfunction "X2_122") (pintype "output"))
      (node (ref "Y1") (pin "3") (pinfunction "3_3") (pintype "passive"))
    )
    (net (code "86") (name "unconnected-(U3A-FXSD4-Pad39)") (class "Default")
      (node (ref "U3") (pin "39") (pinfunction "FXSD4_39") (pintype "input"))
    )
    (net (code "87") (name "unconnected-(U3A-FXSD5{slash}FXSD3-Pad38)") (class "Default")
      (node (ref "U3") (pin "38") (pinfunction "FXSD5/FXSD3_38") (pintype "input"))
    )
    (net (code "88") (name "unconnected-(U3A-MDI-XDIS-Pad1)") (class "Default")
      (node (ref "U3") (pin "1") (pinfunction "MDI-XDIS_1") (pintype "input"))
    )
    (net (code "89") (name "unconnected-(U3A-MUX1-Pad45)") (class "Default")
      (node (ref "U3") (pin "45") (pinfunction "MUX1_45") (pintype "passive"))
    )
    (net (code "90") (name "unconnected-(U3A-MUX2-Pad46)") (class "Default")
      (node (ref "U3") (pin "46") (pinfunction "MUX2_46") (pintype "passive"))
    )
    (net (code "91") (name "unconnected-(U3A-PMRXC-Pad60)") (class "Default")
      (node (ref "U3") (pin "60") (pinfunction "PMRXC_60") (pintype "output"))
    )
    (net (code "92") (name "unconnected-(U3A-PMRXD1-Pad64)") (class "Default")
      (node (ref "U3") (pin "64") (pinfunction "PMRXD1_64") (pintype "bidirectional"))
    )
    (net (code "93") (name "unconnected-(U3A-PMRXD2-Pad63)") (class "Default")
      (node (ref "U3") (pin "63") (pinfunction "PMRXD2_63") (pintype "bidirectional"))
    )
    (net (code "94") (name "unconnected-(U3A-PMRXD3-Pad62)") (class "Default")
      (node (ref "U3") (pin "62") (pinfunction "PMRXD3_62") (pintype "bidirectional"))
    )
    (net (code "95") (name "unconnected-(U3A-PMRXDV-Pad61)") (class "Default")
      (node (ref "U3") (pin "61") (pinfunction "PMRXDV_61") (pintype "bidirectional"))
    )
    (net (code "96") (name "unconnected-(U3A-PMTXC-Pad57)") (class "Default")
      (node (ref "U3") (pin "57") (pinfunction "PMTXC_57") (pintype "output"))
    )
    (net (code "97") (name "unconnected-(U3A-PMTXD0-Pad55)") (class "Default")
      (node (ref "U3") (pin "55") (pinfunction "PMTXD0_55") (pintype "input"))
    )
    (net (code "98") (name "unconnected-(U3A-PMTXD1-Pad54)") (class "Default")
      (node (ref "U3") (pin "54") (pinfunction "PMTXD1_54") (pintype "input"))
    )
    (net (code "99") (name "unconnected-(U3A-PMTXD2-Pad53)") (class "Default")
      (node (ref "U3") (pin "53") (pinfunction "PMTXD2_53") (pintype "input"))
    )
    (net (code "100") (name "unconnected-(U3A-PMTXD3-Pad52)") (class "Default")
      (node (ref "U3") (pin "52") (pinfunction "PMTXD3_52") (pintype "input"))
    )
    (net (code "101") (name "unconnected-(U3A-PMTXEN-Pad51)") (class "Default")
      (node (ref "U3") (pin "51") (pinfunction "PMTXEN_51") (pintype "input"))
    )
    (net (code "102") (name "unconnected-(U3A-PMTXER-Pad56)") (class "Default")
      (node (ref "U3") (pin "56") (pinfunction "PMTXER_56") (pintype "input"))
    )
    (net (code "103") (name "unconnected-(U3A-RESERVE-Pad48)") (class "Default")
      (node (ref "U3") (pin "48") (pinfunction "RESERVE_48") (pintype "passive"))
    )
    (net (code "104") (name "unconnected-(U3B-LED1-2-Pad104)") (class "Default")
      (node (ref "U3") (pin "104") (pinfunction "LED1-2_104") (pintype "bidirectional"))
    )
    (net (code "105") (name "unconnected-(U3B-LED2-2-Pad101)") (class "Default")
      (node (ref "U3") (pin "101") (pinfunction "LED2-2_101") (pintype "bidirectional"))
    )
    (net (code "106") (name "unconnected-(U3B-LED3-2-Pad96)") (class "Default")
      (node (ref "U3") (pin "96") (pinfunction "LED3-2_96") (pintype "bidirectional"))
    )
    (net (code "107") (name "unconnected-(U3B-LED4-0-Pad95)") (class "Default")
      (node (ref "U3") (pin "95") (pinfunction "LED4-0_95") (pintype "bidirectional"))
    )
    (net (code "108") (name "unconnected-(U3B-LED4-1-Pad94)") (class "Default")
      (node (ref "U3") (pin "94") (pinfunction "LED4-1_94") (pintype "bidirectional"))
    )
    (net (code "109") (name "unconnected-(U3B-LED4-2-Pad93)") (class "Default")
      (node (ref "U3") (pin "93") (pinfunction "LED4-2_93") (pintype "bidirectional"))
    )
    (net (code "110") (name "unconnected-(U3B-LED5-0-Pad92)") (class "Default")
      (node (ref "U3") (pin "92") (pinfunction "LED5-0_92") (pintype "bidirectional"))
    )
    (net (code "111") (name "unconnected-(U3B-LED5-1-Pad91)") (class "Default")
      (node (ref "U3") (pin "91") (pinfunction "LED5-1_91") (pintype "bidirectional"))
    )
    (net (code "112") (name "unconnected-(U3B-LED5-2-Pad90)") (class "Default")
      (node (ref "U3") (pin "90") (pinfunction "LED5-2_90") (pintype "bidirectional"))
    )
    (net (code "113") (name "unconnected-(U3B-MDC-Pad107)") (class "Default")
      (node (ref "U3") (pin "107") (pinfunction "MDC_107") (pintype "input"))
    )
    (net (code "114") (name "unconnected-(U3B-MDIO-Pad108)") (class "Default")
      (node (ref "U3") (pin "108") (pinfunction "MDIO_108") (pintype "bidirectional"))
    )
    (net (code "115") (name "unconnected-(U3B-NC-Pad120)") (class "Default")
      (node (ref "U3") (pin "120") (pinfunction "NC_120") (pintype "no_connect"))
    )
    (net (code "116") (name "unconnected-(U3B-PCOL-Pad68)") (class "Default")
      (node (ref "U3") (pin "68") (pinfunction "PCOL_68") (pintype "bidirectional"))
    )
    (net (code "117") (name "unconnected-(U3B-PCRS-Pad67)") (class "Default")
      (node (ref "U3") (pin "67") (pinfunction "PCRS_67") (pintype "bidirectional"))
    )
    (net (code "118") (name "unconnected-(U3B-PMRXD0-Pad65)") (class "Default")
      (node (ref "U3") (pin "65") (pinfunction "PMRXD0_65") (pintype "bidirectional"))
    )
    (net (code "119") (name "unconnected-(U3B-PMRXER-Pad66)") (class "Default")
      (node (ref "U3") (pin "66") (pinfunction "PMRXER_66") (pintype "bidirectional"))
    )
    (net (code "120") (name "unconnected-(U3B-SCANEN-Pad119)") (class "Default")
      (node (ref "U3") (pin "119") (pinfunction "SCANEN_119") (pintype "input"))
    )
    (net (code "121") (name "unconnected-(U3B-SCOL-Pad84)") (class "Default")
      (node (ref "U3") (pin "84") (pinfunction "SCOL_84") (pintype "bidirectional"))
    )
    (net (code "122") (name "unconnected-(U3B-SCONF0-Pad87)") (class "Default")
      (node (ref "U3") (pin "87") (pinfunction "SCONF0_87") (pintype "input"))
    )
    (net (code "123") (name "unconnected-(U3B-SCONF1-Pad86)") (class "Default")
      (node (ref "U3") (pin "86") (pinfunction "SCONF1_86") (pintype "input"))
    )
    (net (code "124") (name "unconnected-(U3B-SCRS-Pad85)") (class "Default")
      (node (ref "U3") (pin "85") (pinfunction "SCRS_85") (pintype "bidirectional"))
    )
    (net (code "125") (name "unconnected-(U3B-SMRXC-Pad78)") (class "Default")
      (node (ref "U3") (pin "78") (pinfunction "SMRXC_78") (pintype "bidirectional"))
    )
    (net (code "126") (name "unconnected-(U3B-SMRXD0-Pad83)") (class "Default")
      (node (ref "U3") (pin "83") (pinfunction "SMRXD0_83") (pintype "bidirectional"))
    )
    (net (code "127") (name "unconnected-(U3B-SMRXD1-Pad82)") (class "Default")
      (node (ref "U3") (pin "82") (pinfunction "SMRXD1_82") (pintype "bidirectional"))
    )
    (net (code "128") (name "unconnected-(U3B-SMRXD2-Pad81)") (class "Default")
      (node (ref "U3") (pin "81") (pinfunction "SMRXD2_81") (pintype "bidirectional"))
    )
    (net (code "129") (name "unconnected-(U3B-SMRXD3-Pad80)") (class "Default")
      (node (ref "U3") (pin "80") (pinfunction "SMRXD3_80") (pintype "bidirectional"))
    )
    (net (code "130") (name "unconnected-(U3B-SMRXDV-Pad79)") (class "Default")
      (node (ref "U3") (pin "79") (pinfunction "SMRXDV_79") (pintype "bidirectional"))
    )
    (net (code "131") (name "unconnected-(U3B-SMTXC-Pad75)") (class "Default")
      (node (ref "U3") (pin "75") (pinfunction "SMTXC_75") (pintype "bidirectional"))
    )
    (net (code "132") (name "unconnected-(U3B-SMTXD0-Pad73)") (class "Default")
      (node (ref "U3") (pin "73") (pinfunction "SMTXD0_73") (pintype "input"))
    )
    (net (code "133") (name "unconnected-(U3B-SMTXD1-Pad72)") (class "Default")
      (node (ref "U3") (pin "72") (pinfunction "SMTXD1_72") (pintype "input"))
    )
    (net (code "134") (name "unconnected-(U3B-SMTXD2-Pad71)") (class "Default")
      (node (ref "U3") (pin "71") (pinfunction "SMTXD2_71") (pintype "input"))
    )
    (net (code "135") (name "unconnected-(U3B-SMTXD3-Pad70)") (class "Default")
      (node (ref "U3") (pin "70") (pinfunction "SMTXD3_70") (pintype "input"))
    )
    (net (code "136") (name "unconnected-(U3B-SMTXEN-Pad69)") (class "Default")
      (node (ref "U3") (pin "69") (pinfunction "SMTXEN_69") (pintype "input"))
    )
    (net (code "137") (name "unconnected-(U3B-SMTXER-Pad74)") (class "Default")
      (node (ref "U3") (pin "74") (pinfunction "SMTXER_74") (pintype "input"))
    )
    (net (code "138") (name "unconnected-(U3B-TEST2-Pad128)") (class "Default")
      (node (ref "U3") (pin "128") (pinfunction "TEST2_128") (pintype "passive"))
    )
    (net (code "139") (name "unconnected-(U3B-TESTEN-Pad118)") (class "Default")
      (node (ref "U3") (pin "118") (pinfunction "TESTEN_118") (pintype "input"))
    )
  )
)
